# ESP32-S3_4G_LTE_CAT1_V1_2.net
KiCad netlist of a schematic drawn in EAGLE
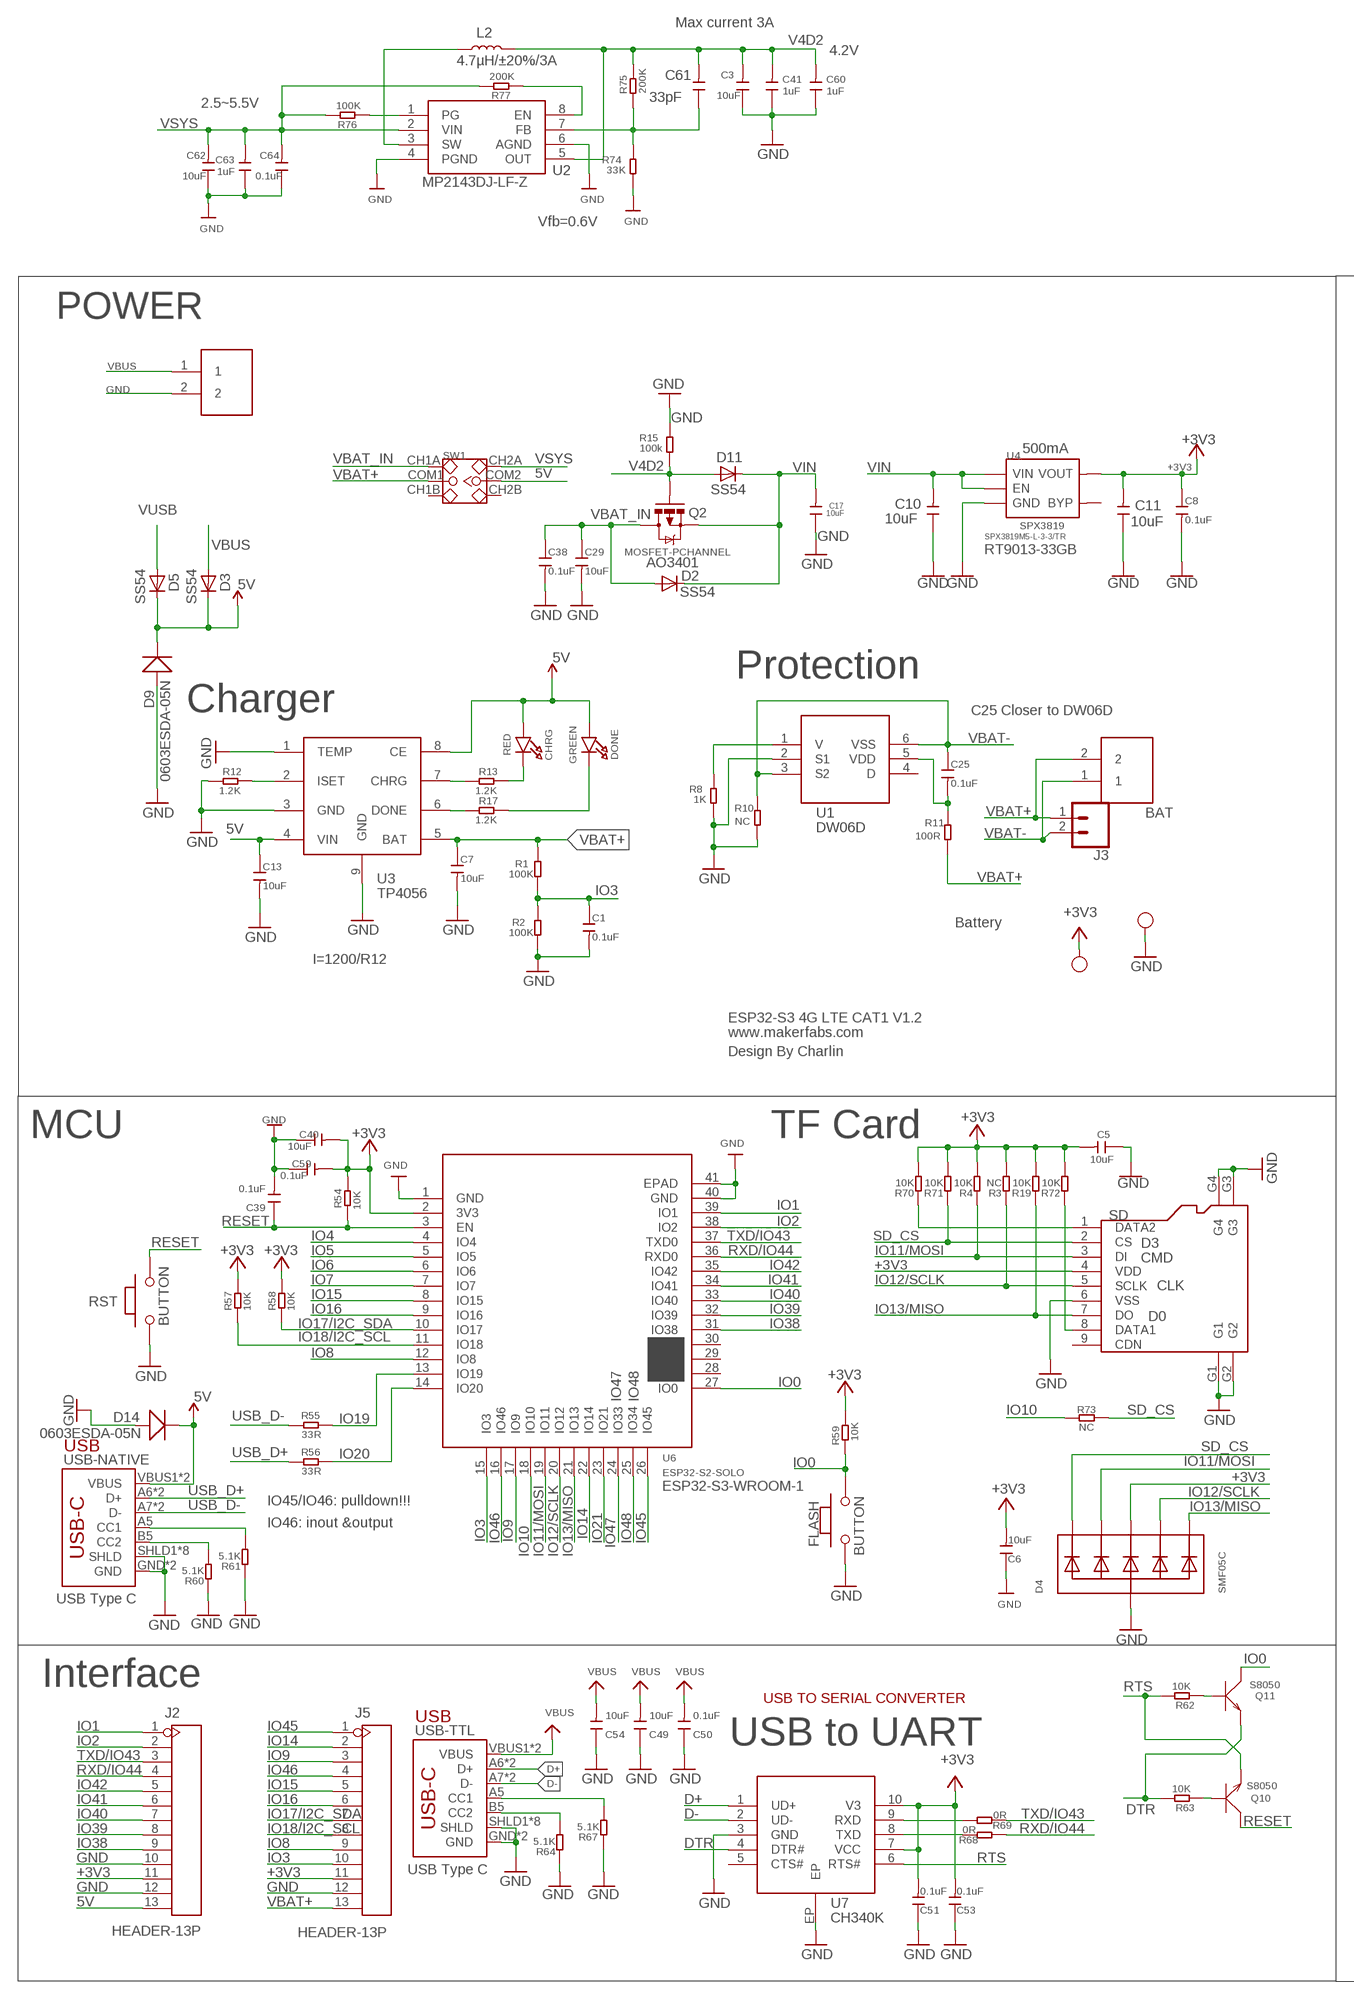
[diagram p0: schematic, sheet 1, part 1 of 2]
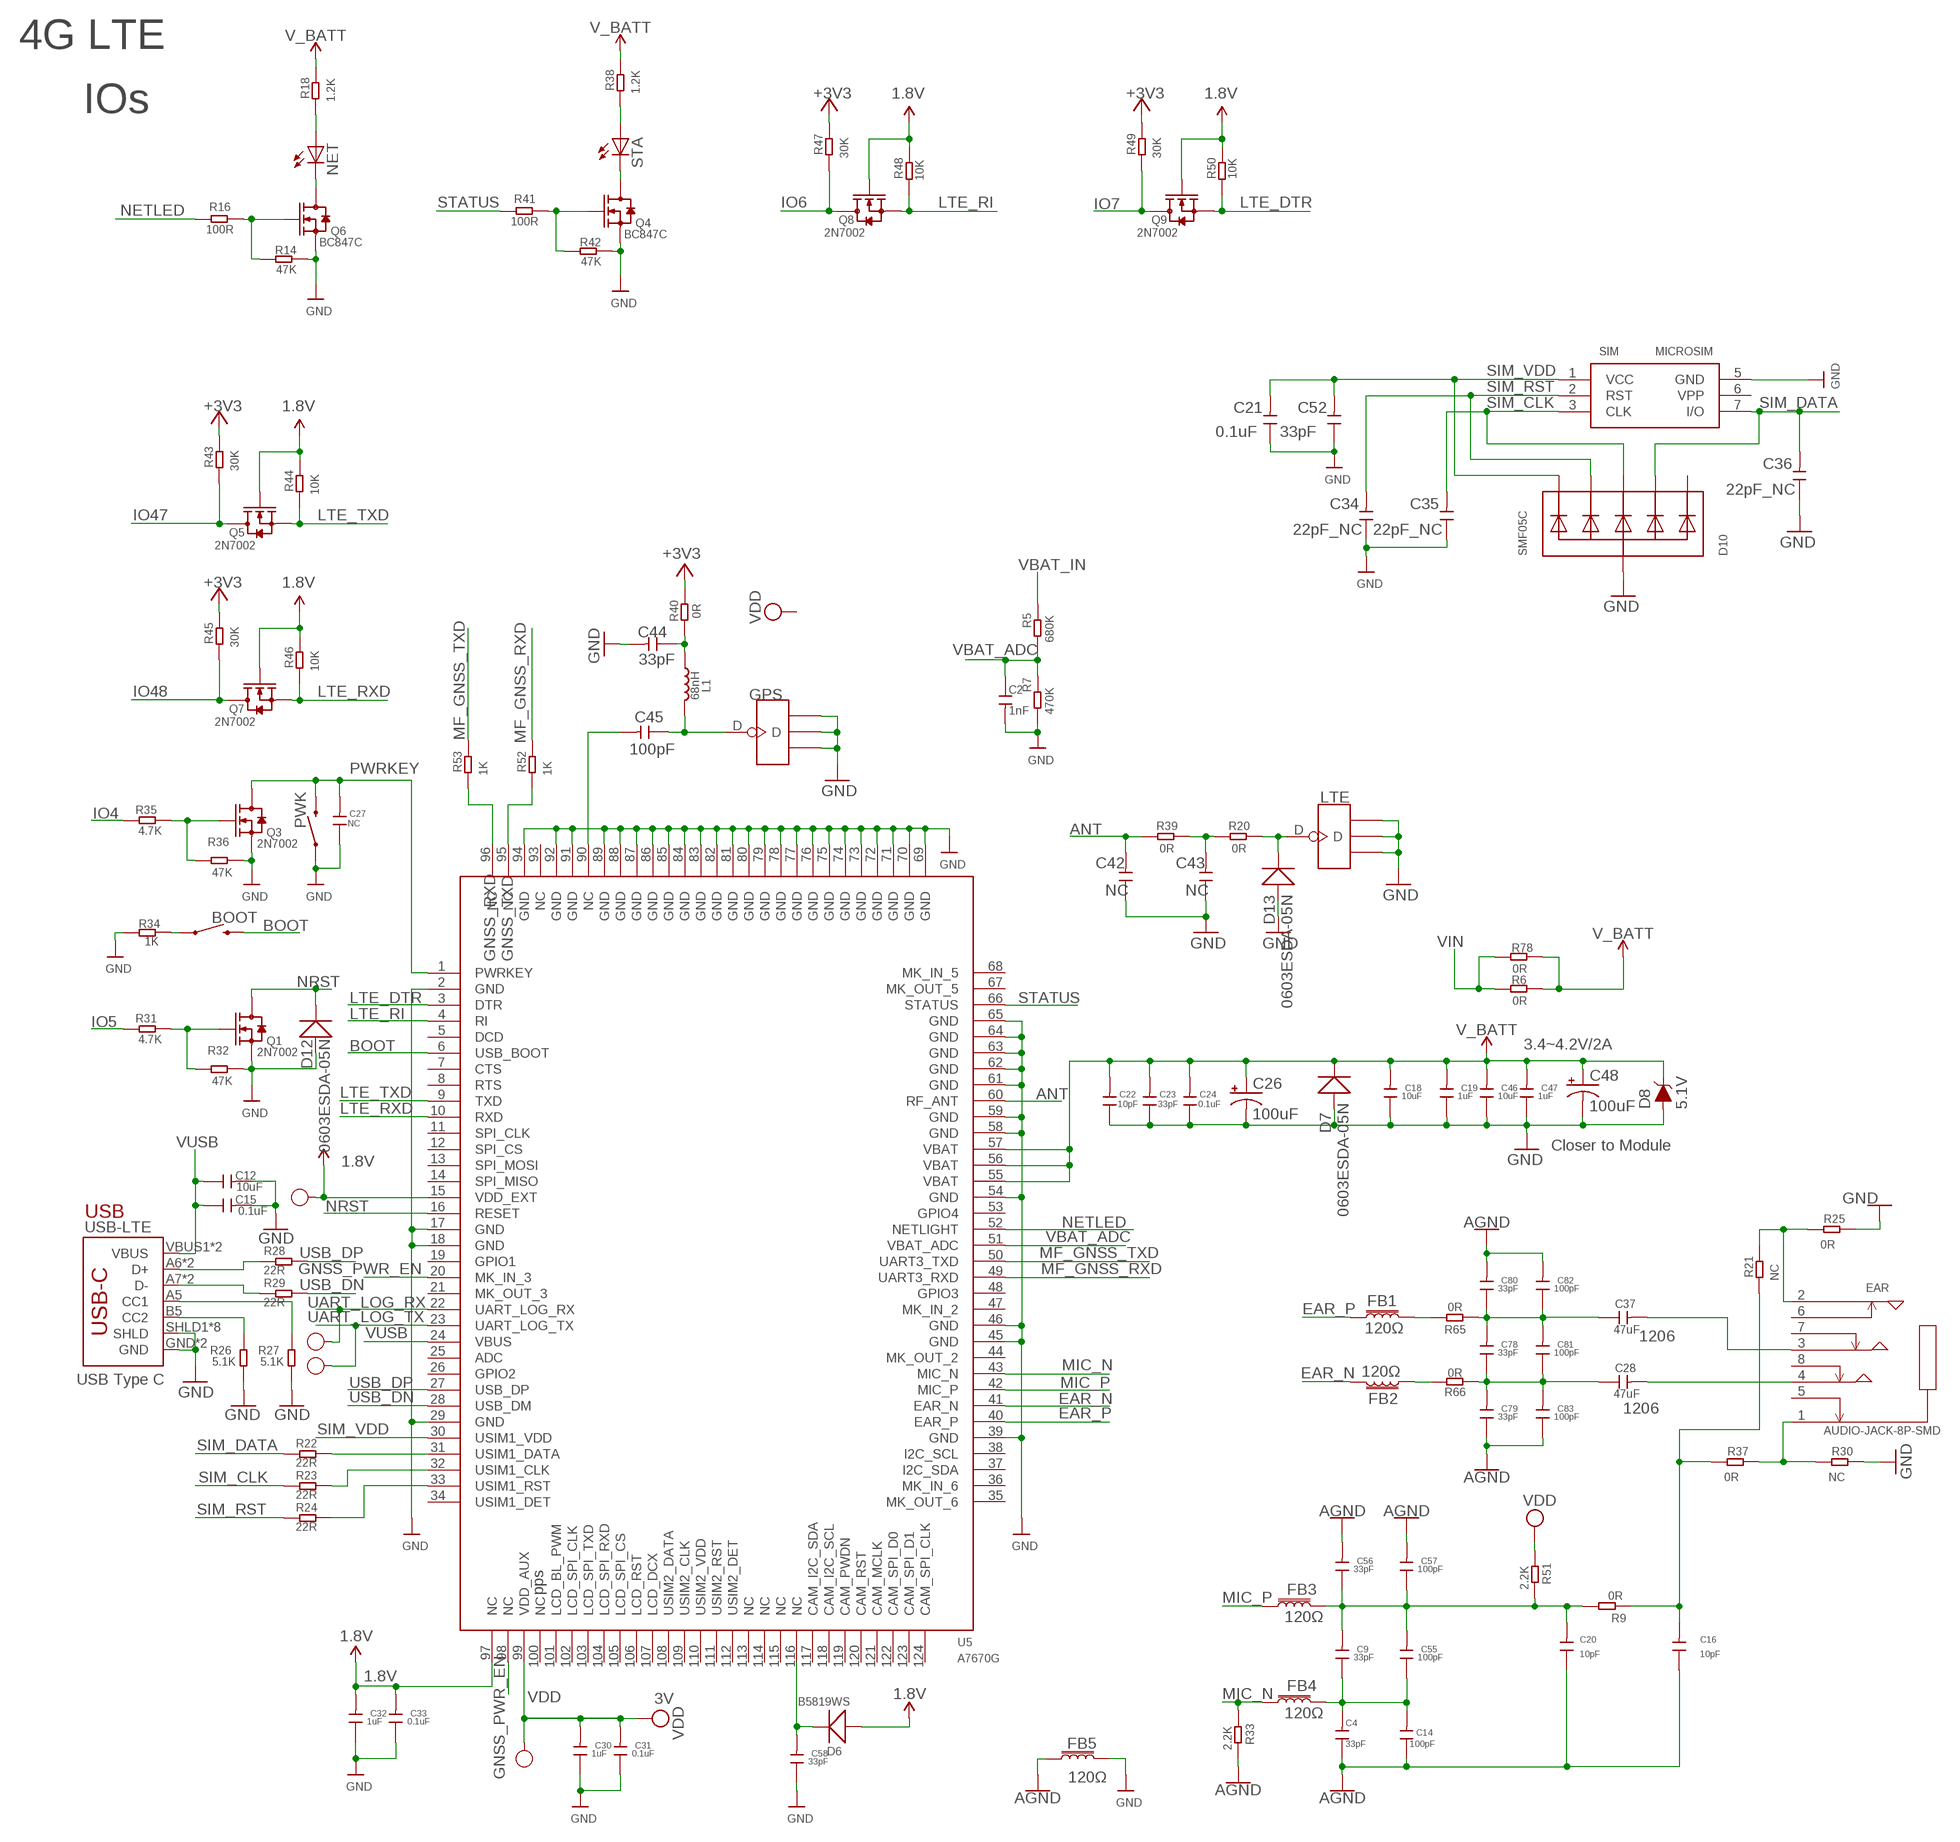
[diagram p1: schematic, sheet 1, part 2 of 2]

(export (version "E")
  (design (tool "Eeschema 10.0.6"))
  (components
    (comp (ref "1V8")
      (value "TEST-POINT'4545'")
      (footprint "eagle-import:TP-D45MIL")
      (fields (field (name "PARTNO") "DNP") (field (name "PARTNO_1") "DNP"))
      (libsource (lib "eagle-import") (part "TEST-POINT'4545'"))
    )
    (comp (ref "3V")
      (value "TEST-POINT'4545'")
      (footprint "eagle-import:TP-D45MIL")
      (fields (field (name "PARTNO") "DNP") (field (name "PARTNO_1") "DNP"))
      (libsource (lib "eagle-import") (part "TEST-POINT'4545'"))
    )
    (comp (ref "3V3")
      (value "TEST-POINT'4545'")
      (footprint "eagle-import:TP-D45MIL")
      (fields (field (name "PARTNO") "DNP") (field (name "PARTNO_1") "DNP"))
      (libsource (lib "eagle-import") (part "TEST-POINT'4545'"))
    )
    (comp (ref "BAT")
      (value "PH2.0-2P-90-DIP")
      (footprint "eagle-import:PH2.0-2P-90-DIP")
      (libsource (lib "eagle-import") (part "PH2.0-2P-90-DIP"))
    )
    (comp (ref "BOOT")
      (value "MOMENTARY-SWITCH-SPST-SMD-6.0X3.5MM")
      (footprint "eagle-import:TACTILE_SWITCH_SMD_6.0X3.5MM")
      (fields (field (name "PROD_ID") "SWCH-00815") (field (name "SF_SKU") "COM-08229"))
      (libsource (lib "eagle-import") (part "MOMENTARY-SWITCH-SPST-SMD-6.0X3.5MM"))
    )
    (comp (ref "C1")
      (value "0.1uF")
      (footprint "eagle-import:0603")
      (libsource (lib "eagle-import") (part "C-0603"))
    )
    (comp (ref "C2")
      (value "1nF")
      (footprint "eagle-import:0603")
      (libsource (lib "eagle-import") (part "C-0603"))
    )
    (comp (ref "C3")
      (value "10uF")
      (footprint "eagle-import:0603")
      (libsource (lib "eagle-import") (part "C-0603"))
    )
    (comp (ref "C4")
      (value "33pF")
      (footprint "eagle-import:0603")
      (libsource (lib "eagle-import") (part "C-0603"))
    )
    (comp (ref "C5")
      (value "10uF")
      (footprint "eagle-import:DISCRETE_C0603")
      (libsource (lib "eagle-import") (part "DISCRETE_C-0603"))
    )
    (comp (ref "C6")
      (value "10uF")
      (footprint "eagle-import:DISCRETE_C0603")
      (libsource (lib "eagle-import") (part "DISCRETE_C-0603"))
    )
    (comp (ref "C7")
      (value "10uF")
      (footprint "eagle-import:0603")
      (libsource (lib "eagle-import") (part "C-0603"))
    )
    (comp (ref "C8")
      (value "0.1uF")
      (footprint "eagle-import:0603")
      (libsource (lib "eagle-import") (part "C-0603"))
    )
    (comp (ref "C9")
      (value "33pF")
      (footprint "eagle-import:0603")
      (libsource (lib "eagle-import") (part "C-0603"))
    )
    (comp (ref "C10")
      (value "10uF")
      (footprint "eagle-import:0603")
      (libsource (lib "eagle-import") (part "C-0603"))
    )
    (comp (ref "C11")
      (value "10uF")
      (footprint "eagle-import:0603")
      (libsource (lib "eagle-import") (part "C-0603"))
    )
    (comp (ref "C12")
      (value "10uF")
      (footprint "eagle-import:0603")
      (libsource (lib "eagle-import") (part "C-0603"))
    )
    (comp (ref "C13")
      (value "10uF")
      (footprint "eagle-import:0603")
      (libsource (lib "eagle-import") (part "C-0603"))
    )
    (comp (ref "C14")
      (value "100pF")
      (footprint "eagle-import:0603")
      (libsource (lib "eagle-import") (part "C-0603"))
    )
    (comp (ref "C15")
      (value "0.1uF")
      (footprint "eagle-import:0603")
      (libsource (lib "eagle-import") (part "C-0603"))
    )
    (comp (ref "C16")
      (value "10pF")
      (footprint "eagle-import:0603")
      (libsource (lib "eagle-import") (part "C-0603"))
    )
    (comp (ref "C17")
      (value "10uF")
      (footprint "eagle-import:0603")
      (libsource (lib "eagle-import") (part "C-0603"))
    )
    (comp (ref "C18")
      (value "10uF")
      (footprint "eagle-import:0603")
      (libsource (lib "eagle-import") (part "C-0603"))
    )
    (comp (ref "C19")
      (value "1uF")
      (footprint "eagle-import:0603")
      (libsource (lib "eagle-import") (part "C-0603"))
    )
    (comp (ref "C20")
      (value "10pF")
      (footprint "eagle-import:0603")
      (libsource (lib "eagle-import") (part "C-0603"))
    )
    (comp (ref "C21")
      (value "0.1uF")
      (footprint "eagle-import:0603")
      (libsource (lib "eagle-import") (part "C-0603"))
    )
    (comp (ref "C22")
      (value "10pF")
      (footprint "eagle-import:0603")
      (libsource (lib "eagle-import") (part "C-0603"))
    )
    (comp (ref "C23")
      (value "33pF")
      (footprint "eagle-import:0603")
      (libsource (lib "eagle-import") (part "C-0603"))
    )
    (comp (ref "C24")
      (value "0.1uF")
      (footprint "eagle-import:0603")
      (libsource (lib "eagle-import") (part "C-0603"))
    )
    (comp (ref "C25")
      (value "0.1uF")
      (footprint "eagle-import:0603")
      (libsource (lib "eagle-import") (part "C-0603"))
    )
    (comp (ref "C26")
      (value "100uF")
      (footprint "eagle-import:EIA3528")
      (fields (field (name "PROD_ID") "CAP-10790"))
      (libsource (lib "eagle-import") (part "68UF-POLAR-EIA3528-10V-10%(TANT)"))
    )
    (comp (ref "C27")
      (value "NC")
      (footprint "eagle-import:0603")
      (libsource (lib "eagle-import") (part "C-0603"))
    )
    (comp (ref "C28")
      (value "47uF")
      (footprint "eagle-import:DISCRETE_C1206")
      (libsource (lib "eagle-import") (part "DISCRETE_C-1206"))
    )
    (comp (ref "C29")
      (value "10uF")
      (footprint "eagle-import:0603")
      (libsource (lib "eagle-import") (part "C-0603"))
    )
    (comp (ref "C30")
      (value "1uF")
      (footprint "eagle-import:0603")
      (libsource (lib "eagle-import") (part "C-0603"))
    )
    (comp (ref "C31")
      (value "0.1uF")
      (footprint "eagle-import:0603")
      (libsource (lib "eagle-import") (part "C-0603"))
    )
    (comp (ref "C32")
      (value "1uF")
      (footprint "eagle-import:0603")
      (libsource (lib "eagle-import") (part "C-0603"))
    )
    (comp (ref "C33")
      (value "0.1uF")
      (footprint "eagle-import:0603")
      (libsource (lib "eagle-import") (part "C-0603"))
    )
    (comp (ref "C34")
      (value "22pF_NC")
      (footprint "eagle-import:0603")
      (libsource (lib "eagle-import") (part "C-0603"))
    )
    (comp (ref "C35")
      (value "22pF_NC")
      (footprint "eagle-import:0603")
      (libsource (lib "eagle-import") (part "C-0603"))
    )
    (comp (ref "C36")
      (value "22pF_NC")
      (footprint "eagle-import:0603")
      (libsource (lib "eagle-import") (part "C-0603"))
    )
    (comp (ref "C37")
      (value "47uF")
      (footprint "eagle-import:DISCRETE_C1206")
      (libsource (lib "eagle-import") (part "DISCRETE_C-1206"))
    )
    (comp (ref "C38")
      (value "0.1uF")
      (footprint "eagle-import:0603")
      (libsource (lib "eagle-import") (part "C-0603"))
    )
    (comp (ref "C39")
      (value "0.1uF")
      (footprint "eagle-import:DISCRETE_C0603")
      (libsource (lib "eagle-import") (part "DISCRETE_C-0603"))
    )
    (comp (ref "C40")
      (value "10uF")
      (footprint "eagle-import:DISCRETE_C0603")
      (libsource (lib "eagle-import") (part "DISCRETE_C-0603"))
    )
    (comp (ref "C41")
      (value "1uF")
      (footprint "eagle-import:0603")
      (libsource (lib "eagle-import") (part "C-0603"))
    )
    (comp (ref "C42")
      (value "NC")
      (footprint "eagle-import:0603")
      (libsource (lib "eagle-import") (part "C-0603"))
    )
    (comp (ref "C43")
      (value "NC")
      (footprint "eagle-import:0603")
      (libsource (lib "eagle-import") (part "C-0603"))
    )
    (comp (ref "C44")
      (value "33pF")
      (footprint "eagle-import:0603")
      (libsource (lib "eagle-import") (part "C-0603"))
    )
    (comp (ref "C45")
      (value "100pF")
      (footprint "eagle-import:0603")
      (libsource (lib "eagle-import") (part "C-0603"))
    )
    (comp (ref "C46")
      (value "10uF")
      (footprint "eagle-import:0603")
      (libsource (lib "eagle-import") (part "C-0603"))
    )
    (comp (ref "C47")
      (value "1uF")
      (footprint "eagle-import:0603")
      (libsource (lib "eagle-import") (part "C-0603"))
    )
    (comp (ref "C48")
      (value "100uF")
      (footprint "eagle-import:EIA3528")
      (libsource (lib "eagle-import") (part "68UF-POLAR-EIA3528-10V-10%(TANT)"))
    )
    (comp (ref "C49")
      (value "10uF")
      (footprint "eagle-import:DISCRETE_C0603")
      (libsource (lib "eagle-import") (part "DISCRETE_C-0603"))
    )
    (comp (ref "C50")
      (value "0.1uF")
      (footprint "eagle-import:DISCRETE_C0603")
      (libsource (lib "eagle-import") (part "DISCRETE_C-0603"))
    )
    (comp (ref "C51")
      (value "0.1uF")
      (footprint "eagle-import:DISCRETE_C0603")
      (libsource (lib "eagle-import") (part "DISCRETE_C-0603"))
    )
    (comp (ref "C52")
      (value "33pF")
      (footprint "eagle-import:0603")
      (libsource (lib "eagle-import") (part "C-0603"))
    )
    (comp (ref "C53")
      (value "0.1uF")
      (footprint "eagle-import:DISCRETE_C0603")
      (libsource (lib "eagle-import") (part "DISCRETE_C-0603"))
    )
    (comp (ref "C54")
      (value "10uF")
      (footprint "eagle-import:DISCRETE_C0603")
      (libsource (lib "eagle-import") (part "DISCRETE_C-0603"))
    )
    (comp (ref "C55")
      (value "100pF")
      (footprint "eagle-import:0603")
      (libsource (lib "eagle-import") (part "C-0603"))
    )
    (comp (ref "C56")
      (value "33pF")
      (footprint "eagle-import:0603")
      (libsource (lib "eagle-import") (part "C-0603"))
    )
    (comp (ref "C57")
      (value "100pF")
      (footprint "eagle-import:0603")
      (libsource (lib "eagle-import") (part "C-0603"))
    )
    (comp (ref "C58")
      (value "33pF")
      (footprint "eagle-import:0603")
      (libsource (lib "eagle-import") (part "C-0603"))
    )
    (comp (ref "C59")
      (value "0.1uF")
      (footprint "eagle-import:DISCRETE_C0603")
      (libsource (lib "eagle-import") (part "DISCRETE_C-0603"))
    )
    (comp (ref "C60")
      (value "1uF")
      (footprint "eagle-import:0603")
      (libsource (lib "eagle-import") (part "C-0603"))
    )
    (comp (ref "C61")
      (value "33pF")
      (footprint "eagle-import:0603")
      (libsource (lib "eagle-import") (part "C-0603"))
    )
    (comp (ref "C62")
      (value "10uF")
      (footprint "eagle-import:0603")
      (libsource (lib "eagle-import") (part "C-0603"))
    )
    (comp (ref "C63")
      (value "1uF")
      (footprint "eagle-import:0603")
      (libsource (lib "eagle-import") (part "C-0603"))
    )
    (comp (ref "C64")
      (value "0.1uF")
      (footprint "eagle-import:0603")
      (libsource (lib "eagle-import") (part "C-0603"))
    )
    (comp (ref "C78")
      (value "33pF")
      (footprint "eagle-import:0603")
      (libsource (lib "eagle-import") (part "C-0603"))
    )
    (comp (ref "C79")
      (value "33pF")
      (footprint "eagle-import:0603")
      (libsource (lib "eagle-import") (part "C-0603"))
    )
    (comp (ref "C80")
      (value "33pF")
      (footprint "eagle-import:0603")
      (libsource (lib "eagle-import") (part "C-0603"))
    )
    (comp (ref "C81")
      (value "100pF")
      (footprint "eagle-import:0603")
      (libsource (lib "eagle-import") (part "C-0603"))
    )
    (comp (ref "C82")
      (value "100pF")
      (footprint "eagle-import:0603")
      (libsource (lib "eagle-import") (part "C-0603"))
    )
    (comp (ref "C83")
      (value "100pF")
      (footprint "eagle-import:0603")
      (libsource (lib "eagle-import") (part "C-0603"))
    )
    (comp (ref "CHRG")
      (value "RED")
      (footprint "eagle-import:CHIPLED_0805_NOOUTLINE")
      (libsource (lib "eagle-import") (part "LED0805_NOOUTLINE"))
    )
    (comp (ref "D2")
      (value "SS54")
      (footprint "eagle-import:DO-214AC")
      (libsource (lib "eagle-import") (part "DIODE-DO-214AC"))
    )
    (comp (ref "D3")
      (value "SS54")
      (footprint "eagle-import:DO-214AC")
      (libsource (lib "eagle-import") (part "DIODE-DO-214AC"))
    )
    (comp (ref "D4")
      (value "SMF05C")
      (footprint "eagle-import:SOT363")
      (libsource (lib "eagle-import") (part "TVSARRAY_5LANE"))
    )
    (comp (ref "D5")
      (value "SS54")
      (footprint "eagle-import:DO-214AC")
      (libsource (lib "eagle-import") (part "DIODE-DO-214AC"))
    )
    (comp (ref "D6")
      (value "B5819WS")
      (footprint "eagle-import:SOD323")
      (libsource (lib "eagle-import") (part "D'0805'"))
    )
    (comp (ref "D7")
      (value "0603ESDA-05N")
      (footprint "eagle-import:DISCRETE_SOD523")
      (libsource (lib "eagle-import") (part "DISCRETE_D0603"))
    )
    (comp (ref "D8")
      (value "5.1V")
      (footprint "eagle-import:SOD-323")
      (libsource (lib "eagle-import") (part "DIODE-ZENER-MMSZ5232BS"))
    )
    (comp (ref "D9")
      (value "0603ESDA-05N")
      (footprint "eagle-import:DISCRETE_SOD523")
      (libsource (lib "eagle-import") (part "DISCRETE_D0603"))
    )
    (comp (ref "D10")
      (value "SMF05C")
      (footprint "eagle-import:SOT363")
      (libsource (lib "eagle-import") (part "TVSARRAY_5LANE"))
    )
    (comp (ref "D11")
      (value "SS54")
      (footprint "eagle-import:DO-214AC")
      (libsource (lib "eagle-import") (part "DIODE-DO-214AC"))
    )
    (comp (ref "D12")
      (value "0603ESDA-05N")
      (footprint "eagle-import:DISCRETE_SOD523")
      (libsource (lib "eagle-import") (part "DISCRETE_D0603"))
    )
    (comp (ref "D13")
      (value "0603ESDA-05N")
      (footprint "eagle-import:DISCRETE_SOD523")
      (libsource (lib "eagle-import") (part "DISCRETE_D0603"))
    )
    (comp (ref "D14")
      (value "0603ESDA-05N")
      (footprint "eagle-import:DISCRETE_SOD523")
      (libsource (lib "eagle-import") (part "DISCRETE_D0603"))
    )
    (comp (ref "DONE")
      (value "GREEN")
      (footprint "eagle-import:CHIPLED_0805_NOOUTLINE")
      (libsource (lib "eagle-import") (part "LED0805_NOOUTLINE"))
    )
    (comp (ref "EAR")
      (value "AUDIO-JACK-8P-SMD")
      (footprint "eagle-import:AUDIO8P-SMD-3.5-14.5X6.1X4.0MM")
      (libsource (lib "eagle-import") (part "AUDIO-JACK-8P-SMD'PJ-393'"))
    )
    (comp (ref "FB1")
      (value "120Ω")
      (footprint "eagle-import:0603")
      (libsource (lib "eagle-import") (part "FERRITE_BEAD-0603"))
    )
    (comp (ref "FB2")
      (value "120Ω")
      (footprint "eagle-import:0603")
      (fields (field (name "PROD_ID") "NDUC-13805"))
      (libsource (lib "eagle-import") (part "FERRITE_BEAD-0603"))
    )
    (comp (ref "FB3")
      (value "120Ω")
      (footprint "eagle-import:0603")
      (fields (field (name "PROD_ID") "NDUC-13805"))
      (libsource (lib "eagle-import") (part "FERRITE_BEAD-0603"))
    )
    (comp (ref "FB4")
      (value "120Ω")
      (footprint "eagle-import:0603")
      (fields (field (name "PROD_ID") "NDUC-13805"))
      (libsource (lib "eagle-import") (part "FERRITE_BEAD-0603"))
    )
    (comp (ref "FB5")
      (value "120Ω")
      (footprint "eagle-import:0603")
      (fields (field (name "PROD_ID") "NDUC-13805"))
      (libsource (lib "eagle-import") (part "FERRITE_BEAD-0603"))
    )
    (comp (ref "FLASH")
      (value "BUTTON")
      (footprint "eagle-import:157SW")
      (libsource (lib "eagle-import") (part "PB157"))
    )
    (comp (ref "GND")
      (value "TEST-POINT'4545'")
      (footprint "eagle-import:TP-D45MIL")
      (fields (field (name "PARTNO") "DNP") (field (name "PARTNO_1") "DNP"))
      (libsource (lib "eagle-import") (part "TEST-POINT'4545'"))
    )
    (comp (ref "GPS")
      (value "ANTENNA-U-FL")
      (footprint "eagle-import:4P-U-FL")
      (libsource (lib "eagle-import") (part "ANTENNA-U-FL"))
    )
    (comp (ref "J1")
      (value "PH2.0-2P-90-DIP")
      (footprint "eagle-import:PH2.0-2P-90-DIP")
      (libsource (lib "eagle-import") (part "PH2.0-2P-90-DIP"))
    )
    (comp (ref "J2")
      (value "HEADER-13P")
      (footprint "eagle-import:13P-2.54")
      (libsource (lib "eagle-import") (part "HEADER-13P"))
    )
    (comp (ref "J3")
      (value "CONN_02LOCK")
      (footprint "eagle-import:1X02_LOCK")
      (libsource (lib "eagle-import") (part "CONN_02LOCK"))
    )
    (comp (ref "J5")
      (value "HEADER-13P")
      (footprint "eagle-import:13P-2.54")
      (libsource (lib "eagle-import") (part "HEADER-13P"))
    )
    (comp (ref "L1")
      (value "68nH")
      (footprint "eagle-import:L0603")
      (libsource (lib "eagle-import") (part "L'0603'"))
    )
    (comp (ref "L2")
      (value "4.7µH/±20%/3A")
      (footprint "eagle-import:SRN6045")
      (libsource (lib "eagle-import") (part "INDUCTOR-SRN6045-33UH"))
    )
    (comp (ref "LTE")
      (value "ANTENNA-U-FL")
      (footprint "eagle-import:4P-U-FL")
      (libsource (lib "eagle-import") (part "ANTENNA-U-FL"))
    )
    (comp (ref "NET")
      (value "NET")
      (footprint "eagle-import:CHIP-LED0805")
      (libsource (lib "eagle-import") (part "LEDCHIP-LED0805"))
    )
    (comp (ref "PWK")
      (value "MOMENTARY-SWITCH-SPST-SMD-6.0X3.5MM")
      (footprint "eagle-import:TACTILE_SWITCH_SMD_6.0X3.5MM")
      (libsource (lib "eagle-import") (part "MOMENTARY-SWITCH-SPST-SMD-6.0X3.5MM"))
    )
    (comp (ref "Q1")
      (value "2N7002")
      (footprint "eagle-import:SOT23")
      (libsource (lib "eagle-import") (part "MOSFET-N'SOT23'"))
    )
    (comp (ref "Q2")
      (value "MOSFET-PCHANNEL")
      (footprint "eagle-import:SOT23-3")
      (libsource (lib "eagle-import") (part "MOSFET-PCHANNEL"))
    )
    (comp (ref "Q3")
      (value "2N7002")
      (footprint "eagle-import:SOT23")
      (libsource (lib "eagle-import") (part "MOSFET-N'SOT23'"))
    )
    (comp (ref "Q4")
      (value "BC847C")
      (footprint "eagle-import:SOT23")
      (libsource (lib "eagle-import") (part "MOSFET-N'SOT23'"))
    )
    (comp (ref "Q5")
      (value "2N7002")
      (footprint "eagle-import:SOT23")
      (libsource (lib "eagle-import") (part "MOSFET-N'SOT23'"))
    )
    (comp (ref "Q6")
      (value "BC847C")
      (footprint "eagle-import:SOT23")
      (libsource (lib "eagle-import") (part "MOSFET-N'SOT23'"))
    )
    (comp (ref "Q7")
      (value "2N7002")
      (footprint "eagle-import:SOT23")
      (libsource (lib "eagle-import") (part "MOSFET-N'SOT23'"))
    )
    (comp (ref "Q8")
      (value "2N7002")
      (footprint "eagle-import:SOT23")
      (libsource (lib "eagle-import") (part "MOSFET-N'SOT23'"))
    )
    (comp (ref "Q9")
      (value "2N7002")
      (footprint "eagle-import:SOT23")
      (libsource (lib "eagle-import") (part "MOSFET-N'SOT23'"))
    )
    (comp (ref "Q10")
      (value "S8050")
      (footprint "eagle-import:SOT23")
      (libsource (lib "eagle-import") (part "TRANSISTOR-NPN-SOT23"))
    )
    (comp (ref "Q11")
      (value "S8050")
      (footprint "eagle-import:SOT23")
      (libsource (lib "eagle-import") (part "TRANSISTOR-NPN-SOT23"))
    )
    (comp (ref "R1")
      (value "100K")
      (footprint "eagle-import:R0603")
      (libsource (lib "eagle-import") (part "R-0603"))
    )
    (comp (ref "R2")
      (value "100K")
      (footprint "eagle-import:R0603")
      (libsource (lib "eagle-import") (part "R-0603"))
    )
    (comp (ref "R3")
      (value "NC")
      (footprint "eagle-import:DISCRETE_R0603")
      (libsource (lib "eagle-import") (part "DISCRETE_R-0603"))
    )
    (comp (ref "R4")
      (value "10K")
      (footprint "eagle-import:DISCRETE_R0603")
      (libsource (lib "eagle-import") (part "DISCRETE_R-0603"))
    )
    (comp (ref "R5")
      (value "680K")
      (footprint "eagle-import:R0603")
      (libsource (lib "eagle-import") (part "R-0603"))
    )
    (comp (ref "R6")
      (value "0R")
      (footprint "eagle-import:R0603")
      (libsource (lib "eagle-import") (part "R-0603"))
    )
    (comp (ref "R7")
      (value "470K")
      (footprint "eagle-import:R0603")
      (libsource (lib "eagle-import") (part "R-0603"))
    )
    (comp (ref "R8")
      (value "1K")
      (footprint "eagle-import:R0603")
      (libsource (lib "eagle-import") (part "R-0603"))
    )
    (comp (ref "R9")
      (value "0R")
      (footprint "eagle-import:R0603")
      (libsource (lib "eagle-import") (part "R-0603"))
    )
    (comp (ref "R10")
      (value "NC")
      (footprint "eagle-import:R0603")
      (libsource (lib "eagle-import") (part "R-0603"))
    )
    (comp (ref "R11")
      (value "100R")
      (footprint "eagle-import:R0603")
      (libsource (lib "eagle-import") (part "R-0603"))
    )
    (comp (ref "R12")
      (value "1.2K")
      (footprint "eagle-import:R0603")
      (libsource (lib "eagle-import") (part "R-0603"))
    )
    (comp (ref "R13")
      (value "1.2K")
      (footprint "eagle-import:R0603")
      (libsource (lib "eagle-import") (part "R-0603"))
    )
    (comp (ref "R14")
      (value "47K")
      (footprint "eagle-import:R0603")
      (libsource (lib "eagle-import") (part "R-0603"))
    )
    (comp (ref "R15")
      (value "100k")
      (footprint "eagle-import:R0603")
      (libsource (lib "eagle-import") (part "R-0603"))
    )
    (comp (ref "R16")
      (value "100R")
      (footprint "eagle-import:R0603")
      (libsource (lib "eagle-import") (part "R-0603"))
    )
    (comp (ref "R17")
      (value "1.2K")
      (footprint "eagle-import:R0603")
      (libsource (lib "eagle-import") (part "R-0603"))
    )
    (comp (ref "R18")
      (value "1.2K")
      (footprint "eagle-import:R0603")
      (libsource (lib "eagle-import") (part "R-0603"))
    )
    (comp (ref "R19")
      (value "10K")
      (footprint "eagle-import:DISCRETE_R0603")
      (libsource (lib "eagle-import") (part "DISCRETE_R-0603"))
    )
    (comp (ref "R20")
      (value "0R")
      (footprint "eagle-import:R0603")
      (libsource (lib "eagle-import") (part "R-0603"))
    )
    (comp (ref "R21")
      (value "NC")
      (footprint "eagle-import:R0603")
      (libsource (lib "eagle-import") (part "R-0603"))
    )
    (comp (ref "R22")
      (value "22R")
      (footprint "eagle-import:R0603")
      (libsource (lib "eagle-import") (part "R-0603"))
    )
    (comp (ref "R23")
      (value "22R")
      (footprint "eagle-import:R0603")
      (libsource (lib "eagle-import") (part "R-0603"))
    )
    (comp (ref "R24")
      (value "22R")
      (footprint "eagle-import:R0603")
      (libsource (lib "eagle-import") (part "R-0603"))
    )
    (comp (ref "R25")
      (value "0R")
      (footprint "eagle-import:R0603")
      (libsource (lib "eagle-import") (part "R-0603"))
    )
    (comp (ref "R26")
      (value "5.1K")
      (footprint "eagle-import:R0603")
      (libsource (lib "eagle-import") (part "R-0603"))
    )
    (comp (ref "R27")
      (value "5.1K")
      (footprint "eagle-import:R0603")
      (libsource (lib "eagle-import") (part "R-0603"))
    )
    (comp (ref "R28")
      (value "22R")
      (footprint "eagle-import:R0603")
      (libsource (lib "eagle-import") (part "R-0603"))
    )
    (comp (ref "R29")
      (value "22R")
      (footprint "eagle-import:R0603")
      (libsource (lib "eagle-import") (part "R-0603"))
    )
    (comp (ref "R30")
      (value "NC")
      (footprint "eagle-import:R0603")
      (libsource (lib "eagle-import") (part "R-0603"))
    )
    (comp (ref "R31")
      (value "4.7K")
      (footprint "eagle-import:R0603")
      (libsource (lib "eagle-import") (part "R-0603"))
    )
    (comp (ref "R32")
      (value "47K")
      (footprint "eagle-import:R0603")
      (libsource (lib "eagle-import") (part "R-0603"))
    )
    (comp (ref "R33")
      (value "2.2K")
      (footprint "eagle-import:R0603")
      (libsource (lib "eagle-import") (part "R-0603"))
    )
    (comp (ref "R34")
      (value "1K")
      (footprint "eagle-import:R0603")
      (libsource (lib "eagle-import") (part "R-0603"))
    )
    (comp (ref "R35")
      (value "4.7K")
      (footprint "eagle-import:R0603")
      (libsource (lib "eagle-import") (part "R-0603"))
    )
    (comp (ref "R36")
      (value "47K")
      (footprint "eagle-import:R0603")
      (libsource (lib "eagle-import") (part "R-0603"))
    )
    (comp (ref "R37")
      (value "0R")
      (footprint "eagle-import:R0603")
      (libsource (lib "eagle-import") (part "R-0603"))
    )
    (comp (ref "R38")
      (value "1.2K")
      (footprint "eagle-import:R0603")
      (libsource (lib "eagle-import") (part "R-0603"))
    )
    (comp (ref "R39")
      (value "0R")
      (footprint "eagle-import:R0603")
      (libsource (lib "eagle-import") (part "R-0603"))
    )
    (comp (ref "R40")
      (value "0R")
      (footprint "eagle-import:R0603")
      (libsource (lib "eagle-import") (part "R-0603"))
    )
    (comp (ref "R41")
      (value "100R")
      (footprint "eagle-import:R0603")
      (libsource (lib "eagle-import") (part "R-0603"))
    )
    (comp (ref "R42")
      (value "47K")
      (footprint "eagle-import:R0603")
      (libsource (lib "eagle-import") (part "R-0603"))
    )
    (comp (ref "R43")
      (value "30K")
      (footprint "eagle-import:R0603")
      (libsource (lib "eagle-import") (part "R-0603"))
    )
    (comp (ref "R44")
      (value "10K")
      (footprint "eagle-import:R0603")
      (libsource (lib "eagle-import") (part "R-0603"))
    )
    (comp (ref "R45")
      (value "30K")
      (footprint "eagle-import:R0603")
      (libsource (lib "eagle-import") (part "R-0603"))
    )
    (comp (ref "R46")
      (value "10K")
      (footprint "eagle-import:R0603")
      (libsource (lib "eagle-import") (part "R-0603"))
    )
    (comp (ref "R47")
      (value "30K")
      (footprint "eagle-import:R0603")
      (libsource (lib "eagle-import") (part "R-0603"))
    )
    (comp (ref "R48")
      (value "10K")
      (footprint "eagle-import:R0603")
      (libsource (lib "eagle-import") (part "R-0603"))
    )
    (comp (ref "R49")
      (value "30K")
      (footprint "eagle-import:R0603")
      (libsource (lib "eagle-import") (part "R-0603"))
    )
    (comp (ref "R50")
      (value "10K")
      (footprint "eagle-import:R0603")
      (libsource (lib "eagle-import") (part "R-0603"))
    )
    (comp (ref "R51")
      (value "2.2K")
      (footprint "eagle-import:R0603")
      (libsource (lib "eagle-import") (part "R-0603"))
    )
    (comp (ref "R52")
      (value "1K")
      (footprint "eagle-import:R0603")
      (libsource (lib "eagle-import") (part "R-0603"))
    )
    (comp (ref "R53")
      (value "1K")
      (footprint "eagle-import:R0603")
      (libsource (lib "eagle-import") (part "R-0603"))
    )
    (comp (ref "R54")
      (value "10K")
      (footprint "eagle-import:R0603")
      (libsource (lib "eagle-import") (part "R-0603"))
    )
    (comp (ref "R55")
      (value "33R")
      (footprint "eagle-import:R0603")
      (libsource (lib "eagle-import") (part "R-0603"))
    )
    (comp (ref "R56")
      (value "33R")
      (footprint "eagle-import:R0603")
      (libsource (lib "eagle-import") (part "R-0603"))
    )
    (comp (ref "R57")
      (value "10K")
      (footprint "eagle-import:R0603")
      (libsource (lib "eagle-import") (part "R-0603"))
    )
    (comp (ref "R58")
      (value "10K")
      (footprint "eagle-import:R0603")
      (libsource (lib "eagle-import") (part "R-0603"))
    )
    (comp (ref "R59")
      (value "10K")
      (footprint "eagle-import:R0603")
      (libsource (lib "eagle-import") (part "R-0603"))
    )
    (comp (ref "R60")
      (value "5.1K")
      (footprint "eagle-import:DISCRETE_R0603")
      (libsource (lib "eagle-import") (part "DISCRETE_R-0603"))
    )
    (comp (ref "R61")
      (value "5.1K")
      (footprint "eagle-import:DISCRETE_R0603")
      (libsource (lib "eagle-import") (part "DISCRETE_R-0603"))
    )
    (comp (ref "R62")
      (value "10K")
      (footprint "eagle-import:R0603")
      (libsource (lib "eagle-import") (part "R-0603"))
    )
    (comp (ref "R63")
      (value "10K")
      (footprint "eagle-import:R0603")
      (libsource (lib "eagle-import") (part "R-0603"))
    )
    (comp (ref "R64")
      (value "5.1K")
      (footprint "eagle-import:DISCRETE_R0603")
      (libsource (lib "eagle-import") (part "DISCRETE_R-0603"))
    )
    (comp (ref "R65")
      (value "0R")
      (footprint "eagle-import:R0603")
      (libsource (lib "eagle-import") (part "R-0603"))
    )
    (comp (ref "R66")
      (value "0R")
      (footprint "eagle-import:R0603")
      (libsource (lib "eagle-import") (part "R-0603"))
    )
    (comp (ref "R67")
      (value "5.1K")
      (footprint "eagle-import:DISCRETE_R0603")
      (libsource (lib "eagle-import") (part "DISCRETE_R-0603"))
    )
    (comp (ref "R68")
      (value "0R")
      (footprint "eagle-import:R0603")
      (libsource (lib "eagle-import") (part "R-0603"))
    )
    (comp (ref "R69")
      (value "0R")
      (footprint "eagle-import:R0603")
      (libsource (lib "eagle-import") (part "R-0603"))
    )
    (comp (ref "R70")
      (value "10K")
      (footprint "eagle-import:DISCRETE_R0603")
      (libsource (lib "eagle-import") (part "DISCRETE_R-0603"))
    )
    (comp (ref "R71")
      (value "10K")
      (footprint "eagle-import:DISCRETE_R0603")
      (libsource (lib "eagle-import") (part "DISCRETE_R-0603"))
    )
    (comp (ref "R72")
      (value "10K")
      (footprint "eagle-import:DISCRETE_R0603")
      (libsource (lib "eagle-import") (part "DISCRETE_R-0603"))
    )
    (comp (ref "R73")
      (value "NC")
      (footprint "eagle-import:R0603")
      (libsource (lib "eagle-import") (part "R-0603"))
    )
    (comp (ref "R74")
      (value "33K")
      (footprint "eagle-import:R0603")
      (libsource (lib "eagle-import") (part "R-0603"))
    )
    (comp (ref "R75")
      (value "200K")
      (footprint "eagle-import:R0603")
      (libsource (lib "eagle-import") (part "R-0603"))
    )
    (comp (ref "R76")
      (value "100K")
      (footprint "eagle-import:R0603")
      (libsource (lib "eagle-import") (part "R-0603"))
    )
    (comp (ref "R77")
      (value "200K")
      (footprint "eagle-import:R0603")
      (libsource (lib "eagle-import") (part "R-0603"))
    )
    (comp (ref "R78")
      (value "0R")
      (footprint "eagle-import:R0603")
      (libsource (lib "eagle-import") (part "R-0603"))
    )
    (comp (ref "RST")
      (value "BUTTON")
      (footprint "eagle-import:157SW")
      (libsource (lib "eagle-import") (part "PB157"))
    )
    (comp (ref "RX")
      (value "TEST-POINT'4545'")
      (footprint "eagle-import:TP-D45MIL")
      (fields (field (name "PARTNO") "DNP") (field (name "PARTNO_1") "DNP"))
      (libsource (lib "eagle-import") (part "TEST-POINT'4545'"))
    )
    (comp (ref "SD")
      (value "HOLDER-MICROSD-9P")
      (footprint "eagle-import:9P-SMD-W_-RING")
      (libsource (lib "eagle-import") (part "HOLDER-MICROSD-9P"))
    )
    (comp (ref "SIM")
      (value "MICROSIM")
      (footprint "eagle-import:MICROSIM")
      (libsource (lib "eagle-import") (part "MICROSIM"))
    )
    (comp (ref "STA")
      (value "NET")
      (footprint "eagle-import:CHIP-LED0805")
      (libsource (lib "eagle-import") (part "LEDCHIP-LED0805"))
    )
    (comp (ref "SW1")
      (value "SWITCH-2CH-6P")
      (footprint "eagle-import:6P-2CH-2.54-7.6X3.0")
      (libsource (lib "eagle-import") (part "SWITCH-2CH-6P"))
    )
    (comp (ref "TX")
      (value "TEST-POINT'4545'")
      (footprint "eagle-import:TP-D45MIL")
      (fields (field (name "PARTNO") "DNP") (field (name "PARTNO_1") "DNP"))
      (libsource (lib "eagle-import") (part "TEST-POINT'4545'"))
    )
    (comp (ref "U1")
      (value "DW06D")
      (footprint "eagle-import:SOT-23-6")
      (libsource (lib "eagle-import") (part "DW06D"))
    )
    (comp (ref "U2")
      (value "MP2143DJ-LF-Z")
      (footprint "eagle-import:TSOT23-8")
      (libsource (lib "eagle-import") (part "MP2143DJ-LF-Z"))
    )
    (comp (ref "U3")
      (value "TP4056")
      (footprint "eagle-import:SOP8-1.27P")
      (libsource (lib "eagle-import") (part "TP4056"))
    )
    (comp (ref "U4")
      (value "SPX3819")
      (footprint "eagle-import:SOT23-5")
      (libsource (lib "eagle-import") (part "SPX3819"))
    )
    (comp (ref "U5")
      (value "A7670G")
      (footprint "eagle-import:A7670G")
      (libsource (lib "eagle-import") (part "A7670G"))
    )
    (comp (ref "U6")
      (value "ESP32­S2­SOLO")
      (footprint "eagle-import:ESP32-­S2-­SOLO")
      (libsource (lib "eagle-import") (part "ESP32­S2­SOLO"))
    )
    (comp (ref "U7")
      (value "CH340K")
      (footprint "eagle-import:ESOP-10-EP-150MIL")
      (libsource (lib "eagle-import") (part "CH340K"))
    )
    (comp (ref "USB-LTE")
      (value "USB_C5")
      (footprint "eagle-import:USB-C-16P-5")
      (libsource (lib "eagle-import") (part "USB_C5"))
    )
    (comp (ref "USB-NATIVE")
      (value "USB_C5")
      (footprint "eagle-import:USB-C-16P-5")
      (libsource (lib "eagle-import") (part "USB_C5"))
    )
    (comp (ref "USB-TTL")
      (value "USB_C5")
      (footprint "eagle-import:USB-C-16P-5")
      (libsource (lib "eagle-import") (part "USB_C5"))
    )
  )
  (nets
    (net (code "1") (name "+3V3") (class "Default")
      (node (ref "3V3") (pin "T") (pinfunction "T_T") (pintype "bidirectional"))
      (node (ref "C11") (pin "2") (pinfunction "2_2") (pintype "passive"))
      (node (ref "C40") (pin "2") (pinfunction "2_2") (pintype "passive"))
      (node (ref "C5") (pin "2") (pinfunction "2_2") (pintype "passive"))
      (node (ref "C51") (pin "2") (pinfunction "2_2") (pintype "passive"))
      (node (ref "C53") (pin "2") (pinfunction "2_2") (pintype "passive"))
      (node (ref "C59") (pin "2") (pinfunction "2_2") (pintype "passive"))
      (node (ref "C6") (pin "2") (pinfunction "2_2") (pintype "passive"))
      (node (ref "C8") (pin "1") (pinfunction "1_1") (pintype "passive"))
      (node (ref "D4") (pin "4") (pinfunction "C3_4") (pintype "passive"))
      (node (ref "J2") (pin "11") (pinfunction "11_11") (pintype "bidirectional"))
      (node (ref "J5") (pin "11") (pinfunction "11_11") (pintype "bidirectional"))
      (node (ref "R19") (pin "2") (pinfunction "2_2") (pintype "passive"))
      (node (ref "R3") (pin "2") (pinfunction "2_2") (pintype "passive"))
      (node (ref "R4") (pin "2") (pinfunction "2_2") (pintype "passive"))
      (node (ref "R40") (pin "2") (pinfunction "2_2") (pintype "passive"))
      (node (ref "R43") (pin "2") (pinfunction "2_2") (pintype "passive"))
      (node (ref "R45") (pin "2") (pinfunction "2_2") (pintype "passive"))
      (node (ref "R47") (pin "2") (pinfunction "2_2") (pintype "passive"))
      (node (ref "R49") (pin "2") (pinfunction "2_2") (pintype "passive"))
      (node (ref "R54") (pin "2") (pinfunction "2_2") (pintype "passive"))
      (node (ref "R57") (pin "2") (pinfunction "2_2") (pintype "passive"))
      (node (ref "R58") (pin "2") (pinfunction "2_2") (pintype "passive"))
      (node (ref "R59") (pin "2") (pinfunction "2_2") (pintype "passive"))
      (node (ref "R70") (pin "2") (pinfunction "2_2") (pintype "passive"))
      (node (ref "R71") (pin "2") (pinfunction "2_2") (pintype "passive"))
      (node (ref "R72") (pin "2") (pinfunction "2_2") (pintype "passive"))
      (node (ref "SD") (pin "4") (pinfunction "VDD_4") (pintype "bidirectional"))
      (node (ref "U4") (pin "5") (pinfunction "VOUT_5") (pintype "bidirectional"))
      (node (ref "U6") (pin "2") (pinfunction "3V3_2") (pintype "bidirectional"))
      (node (ref "U7") (pin "10") (pinfunction "V3_10") (pintype "bidirectional"))
      (node (ref "U7") (pin "7") (pinfunction "VCC_7") (pintype "bidirectional"))
    )
    (net (code "2") (name "/ANT") (class "Default")
      (node (ref "C42") (pin "2") (pinfunction "2_2") (pintype "passive"))
      (node (ref "R39") (pin "1") (pinfunction "1_1") (pintype "passive"))
      (node (ref "U5") (pin "60") (pinfunction "RF_ANT_60") (pintype "bidirectional"))
    )
    (net (code "3") (name "/BOOT") (class "Default")
      (node (ref "BOOT") (pin "2") (pinfunction "2_2") (pintype "passive"))
      (node (ref "U5") (pin "6") (pinfunction "USB_BOOT_6") (pintype "bidirectional"))
    )
    (net (code "4") (name "/DTR") (class "Default")
      (node (ref "Q11") (pin "2") (pinfunction "E_2") (pintype "passive"))
      (node (ref "R63") (pin "2") (pinfunction "2_2") (pintype "passive"))
      (node (ref "U7") (pin "4") (pinfunction "DTR#_4") (pintype "bidirectional"))
    )
    (net (code "5") (name "/EAR_N") (class "Default")
      (node (ref "FB2") (pin "2") (pinfunction "2_2") (pintype "passive"))
      (node (ref "U5") (pin "41") (pinfunction "EAR_N_41") (pintype "bidirectional"))
    )
    (net (code "6") (name "/EAR_P") (class "Default")
      (node (ref "FB1") (pin "1") (pinfunction "1_1") (pintype "passive"))
      (node (ref "U5") (pin "40") (pinfunction "EAR_P_40") (pintype "bidirectional"))
    )
    (net (code "7") (name "/GNSS_PWR_EN") (class "Default")
      (node (ref "U5") (pin "20") (pinfunction "MK_IN_3_20") (pintype "bidirectional"))
      (node (ref "U5") (pin "98") (pinfunction "NC_98") (pintype "bidirectional"))
    )
    (net (code "8") (name "/IO0") (class "Default")
      (node (ref "FLASH") (pin "2") (pinfunction "2_2") (pintype "passive"))
      (node (ref "Q11") (pin "3") (pinfunction "C_3") (pintype "passive"))
      (node (ref "R59") (pin "1") (pinfunction "1_1") (pintype "passive"))
      (node (ref "U6") (pin "27") (pinfunction "IO0_27") (pintype "bidirectional"))
    )
    (net (code "9") (name "/IO1") (class "Default")
      (node (ref "J2") (pin "1") (pinfunction "1_1") (pintype "bidirectional"))
      (node (ref "U6") (pin "39") (pinfunction "IO1_39") (pintype "bidirectional"))
    )
    (net (code "10") (name "/IO2") (class "Default")
      (node (ref "J2") (pin "2") (pinfunction "2_2") (pintype "bidirectional"))
      (node (ref "U6") (pin "38") (pinfunction "IO2_38") (pintype "bidirectional"))
    )
    (net (code "11") (name "/IO3") (class "Default")
      (node (ref "C1") (pin "1") (pinfunction "1_1") (pintype "passive"))
      (node (ref "J5") (pin "10") (pinfunction "10_10") (pintype "bidirectional"))
      (node (ref "R1") (pin "1") (pinfunction "1_1") (pintype "passive"))
      (node (ref "R2") (pin "2") (pinfunction "2_2") (pintype "passive"))
      (node (ref "U6") (pin "15") (pinfunction "IO3_15") (pintype "bidirectional"))
    )
    (net (code "12") (name "/IO4") (class "Default")
      (node (ref "R35") (pin "2") (pinfunction "2_2") (pintype "passive"))
      (node (ref "U6") (pin "4") (pinfunction "IO4_4") (pintype "bidirectional"))
    )
    (net (code "13") (name "/IO5") (class "Default")
      (node (ref "R31") (pin "2") (pinfunction "2_2") (pintype "passive"))
      (node (ref "U6") (pin "5") (pinfunction "IO5_5") (pintype "bidirectional"))
    )
    (net (code "14") (name "/IO6") (class "Default")
      (node (ref "Q8") (pin "3") (pinfunction "D_3") (pintype "passive"))
      (node (ref "R47") (pin "1") (pinfunction "1_1") (pintype "passive"))
      (node (ref "U6") (pin "6") (pinfunction "IO6_6") (pintype "bidirectional"))
    )
    (net (code "15") (name "/IO7") (class "Default")
      (node (ref "Q9") (pin "3") (pinfunction "D_3") (pintype "passive"))
      (node (ref "R49") (pin "1") (pinfunction "1_1") (pintype "passive"))
      (node (ref "U6") (pin "7") (pinfunction "IO7_7") (pintype "bidirectional"))
    )
    (net (code "16") (name "/IO8") (class "Default")
      (node (ref "J5") (pin "9") (pinfunction "9_9") (pintype "bidirectional"))
      (node (ref "U6") (pin "12") (pinfunction "IO8_12") (pintype "bidirectional"))
    )
    (net (code "17") (name "/IO9") (class "Default")
      (node (ref "J5") (pin "3") (pinfunction "3_3") (pintype "bidirectional"))
      (node (ref "U6") (pin "17") (pinfunction "IO9_17") (pintype "bidirectional"))
    )
    (net (code "18") (name "/IO10") (class "Default")
      (node (ref "R73") (pin "1") (pinfunction "1_1") (pintype "passive"))
      (node (ref "U6") (pin "18") (pinfunction "IO10_18") (pintype "bidirectional"))
    )
    (net (code "19") (name "/IO11{slash}MOSI") (class "Default")
      (node (ref "D4") (pin "3") (pinfunction "C2_3") (pintype "passive"))
      (node (ref "R4") (pin "1") (pinfunction "1_1") (pintype "passive"))
      (node (ref "SD") (pin "3") (pinfunction "DI_3") (pintype "bidirectional"))
      (node (ref "U6") (pin "19") (pinfunction "IO11_19") (pintype "bidirectional"))
    )
    (net (code "20") (name "/IO12{slash}SCLK") (class "Default")
      (node (ref "D4") (pin "5") (pinfunction "C4_5") (pintype "passive"))
      (node (ref "R3") (pin "1") (pinfunction "1_1") (pintype "passive"))
      (node (ref "SD") (pin "5") (pinfunction "SCLK_5") (pintype "bidirectional"))
      (node (ref "U6") (pin "20") (pinfunction "IO12_20") (pintype "bidirectional"))
    )
    (net (code "21") (name "/IO13{slash}MISO") (class "Default")
      (node (ref "D4") (pin "6") (pinfunction "C5_6") (pintype "passive"))
      (node (ref "R19") (pin "1") (pinfunction "1_1") (pintype "passive"))
      (node (ref "SD") (pin "7") (pinfunction "DO_7") (pintype "bidirectional"))
      (node (ref "U6") (pin "21") (pinfunction "IO13_21") (pintype "bidirectional"))
    )
    (net (code "22") (name "/IO14") (class "Default")
      (node (ref "J5") (pin "2") (pinfunction "2_2") (pintype "bidirectional"))
      (node (ref "U6") (pin "22") (pinfunction "IO14_22") (pintype "bidirectional"))
    )
    (net (code "23") (name "/IO15") (class "Default")
      (node (ref "J5") (pin "5") (pinfunction "5_5") (pintype "bidirectional"))
      (node (ref "U6") (pin "8") (pinfunction "IO15_8") (pintype "bidirectional"))
    )
    (net (code "24") (name "/IO16") (class "Default")
      (node (ref "J5") (pin "6") (pinfunction "6_6") (pintype "bidirectional"))
      (node (ref "U6") (pin "9") (pinfunction "IO16_9") (pintype "bidirectional"))
    )
    (net (code "25") (name "/IO17{slash}I2C_SDA") (class "Default")
      (node (ref "J5") (pin "7") (pinfunction "7_7") (pintype "bidirectional"))
      (node (ref "R58") (pin "1") (pinfunction "1_1") (pintype "passive"))
      (node (ref "U6") (pin "10") (pinfunction "IO17_10") (pintype "bidirectional"))
    )
    (net (code "26") (name "/IO18{slash}I2C_SCL") (class "Default")
      (node (ref "J5") (pin "8") (pinfunction "8_8") (pintype "bidirectional"))
      (node (ref "R57") (pin "1") (pinfunction "1_1") (pintype "passive"))
      (node (ref "U6") (pin "11") (pinfunction "IO18_11") (pintype "bidirectional"))
    )
    (net (code "27") (name "/IO19") (class "Default")
      (node (ref "R55") (pin "2") (pinfunction "2_2") (pintype "passive"))
      (node (ref "U6") (pin "13") (pinfunction "IO19_13") (pintype "bidirectional"))
    )
    (net (code "28") (name "/IO20") (class "Default")
      (node (ref "R56") (pin "2") (pinfunction "2_2") (pintype "passive"))
      (node (ref "U6") (pin "14") (pinfunction "IO20_14") (pintype "bidirectional"))
    )
    (net (code "29") (name "/IO21") (class "Default")
      (node (ref "U6") (pin "23") (pinfunction "IO21_23") (pintype "bidirectional"))
    )
    (net (code "30") (name "/IO38") (class "Default")
      (node (ref "J2") (pin "9") (pinfunction "9_9") (pintype "bidirectional"))
      (node (ref "U6") (pin "31") (pinfunction "IO38_31") (pintype "bidirectional"))
    )
    (net (code "31") (name "/IO39") (class "Default")
      (node (ref "J2") (pin "8") (pinfunction "8_8") (pintype "bidirectional"))
      (node (ref "U6") (pin "32") (pinfunction "IO39_32") (pintype "bidirectional"))
    )
    (net (code "32") (name "/IO40") (class "Default")
      (node (ref "J2") (pin "7") (pinfunction "7_7") (pintype "bidirectional"))
      (node (ref "U6") (pin "33") (pinfunction "IO40_33") (pintype "bidirectional"))
    )
    (net (code "33") (name "/IO41") (class "Default")
      (node (ref "J2") (pin "6") (pinfunction "6_6") (pintype "bidirectional"))
      (node (ref "U6") (pin "34") (pinfunction "IO41_34") (pintype "bidirectional"))
    )
    (net (code "34") (name "/IO42") (class "Default")
      (node (ref "J2") (pin "5") (pinfunction "5_5") (pintype "bidirectional"))
      (node (ref "U6") (pin "35") (pinfunction "IO42_35") (pintype "bidirectional"))
    )
    (net (code "35") (name "/IO45") (class "Default")
      (node (ref "J5") (pin "1") (pinfunction "1_1") (pintype "bidirectional"))
      (node (ref "U6") (pin "26") (pinfunction "IO45_26") (pintype "bidirectional"))
    )
    (net (code "36") (name "/IO46") (class "Default")
      (node (ref "J5") (pin "4") (pinfunction "4_4") (pintype "bidirectional"))
      (node (ref "U6") (pin "16") (pinfunction "IO46_16") (pintype "bidirectional"))
    )
    (net (code "37") (name "/IO47") (class "Default")
      (node (ref "Q5") (pin "3") (pinfunction "D_3") (pintype "passive"))
      (node (ref "R43") (pin "1") (pinfunction "1_1") (pintype "passive"))
      (node (ref "U6") (pin "24") (pinfunction "IO33_24") (pintype "bidirectional"))
    )
    (net (code "38") (name "/IO48") (class "Default")
      (node (ref "Q7") (pin "3") (pinfunction "D_3") (pintype "passive"))
      (node (ref "R45") (pin "1") (pinfunction "1_1") (pintype "passive"))
      (node (ref "U6") (pin "25") (pinfunction "IO34_25") (pintype "bidirectional"))
    )
    (net (code "39") (name "/LTE_DTR") (class "Default")
      (node (ref "Q9") (pin "2") (pinfunction "S_2") (pintype "passive"))
      (node (ref "R50") (pin "1") (pinfunction "1_1") (pintype "passive"))
      (node (ref "U5") (pin "3") (pinfunction "DTR_3") (pintype "bidirectional"))
    )
    (net (code "40") (name "/LTE_RI") (class "Default")
      (node (ref "Q8") (pin "2") (pinfunction "S_2") (pintype "passive"))
      (node (ref "R48") (pin "1") (pinfunction "1_1") (pintype "passive"))
      (node (ref "U5") (pin "4") (pinfunction "RI_4") (pintype "bidirectional"))
    )
    (net (code "41") (name "/LTE_RXD") (class "Default")
      (node (ref "Q7") (pin "2") (pinfunction "S_2") (pintype "passive"))
      (node (ref "R46") (pin "1") (pinfunction "1_1") (pintype "passive"))
      (node (ref "U5") (pin "10") (pinfunction "RXD_10") (pintype "bidirectional"))
    )
    (net (code "42") (name "/LTE_TXD") (class "Default")
      (node (ref "Q5") (pin "2") (pinfunction "S_2") (pintype "passive"))
      (node (ref "R44") (pin "1") (pinfunction "1_1") (pintype "passive"))
      (node (ref "U5") (pin "9") (pinfunction "TXD_9") (pintype "bidirectional"))
    )
    (net (code "43") (name "/MF_GNSS_RXD") (class "Default")
      (node (ref "R52") (pin "2") (pinfunction "2_2") (pintype "passive"))
      (node (ref "U5") (pin "49") (pinfunction "UART3_RXD_49") (pintype "bidirectional"))
    )
    (net (code "44") (name "/MF_GNSS_TXD") (class "Default")
      (node (ref "R53") (pin "2") (pinfunction "2_2") (pintype "passive"))
      (node (ref "U5") (pin "50") (pinfunction "UART3_TXD_50") (pintype "bidirectional"))
    )
    (net (code "45") (name "/MIC_N") (class "Default")
      (node (ref "FB4") (pin "1") (pinfunction "1_1") (pintype "passive"))
      (node (ref "R33") (pin "1") (pinfunction "1_1") (pintype "passive"))
      (node (ref "U5") (pin "43") (pinfunction "MIC_N_43") (pintype "bidirectional"))
    )
    (net (code "46") (name "/MIC_P") (class "Default")
      (node (ref "FB3") (pin "1") (pinfunction "1_1") (pintype "passive"))
      (node (ref "U5") (pin "42") (pinfunction "MIC_P_42") (pintype "bidirectional"))
    )
    (net (code "47") (name "/NETLED") (class "Default")
      (node (ref "R16") (pin "2") (pinfunction "2_2") (pintype "passive"))
      (node (ref "U5") (pin "52") (pinfunction "NETLIGHT_52") (pintype "bidirectional"))
    )
    (net (code "48") (name "/NRST") (class "Default")
      (node (ref "D12") (pin "-") (pinfunction "-_-") (pintype "passive"))
      (node (ref "Q1") (pin "3") (pinfunction "D_3") (pintype "passive"))
      (node (ref "U5") (pin "16") (pinfunction "RESET_16") (pintype "bidirectional"))
    )
    (net (code "49") (name "/PWRKEY") (class "Default")
      (node (ref "C27") (pin "2") (pinfunction "2_2") (pintype "passive"))
      (node (ref "PWK") (pin "2") (pinfunction "2_2") (pintype "passive"))
      (node (ref "Q3") (pin "3") (pinfunction "D_3") (pintype "passive"))
      (node (ref "U5") (pin "1") (pinfunction "PWRKEY_1") (pintype "bidirectional"))
    )
    (net (code "50") (name "/RESET") (class "Default")
      (node (ref "C39") (pin "1") (pinfunction "1_1") (pintype "passive"))
      (node (ref "Q10") (pin "3") (pinfunction "C_3") (pintype "passive"))
      (node (ref "R54") (pin "1") (pinfunction "1_1") (pintype "passive"))
      (node (ref "RST") (pin "2") (pinfunction "2_2") (pintype "passive"))
      (node (ref "U6") (pin "3") (pinfunction "EN_3") (pintype "bidirectional"))
    )
    (net (code "51") (name "/RTS") (class "Default")
      (node (ref "Q10") (pin "2") (pinfunction "E_2") (pintype "passive"))
      (node (ref "R62") (pin "2") (pinfunction "2_2") (pintype "passive"))
      (node (ref "U7") (pin "6") (pinfunction "RTS#_6") (pintype "bidirectional"))
    )
    (net (code "52") (name "/RXD{slash}IO44") (class "Default")
      (node (ref "J2") (pin "4") (pinfunction "4_4") (pintype "bidirectional"))
      (node (ref "R68") (pin "1") (pinfunction "1_1") (pintype "passive"))
      (node (ref "U6") (pin "36") (pinfunction "RXD0_36") (pintype "bidirectional"))
    )
    (net (code "53") (name "/SD_CS") (class "Default")
      (node (ref "D4") (pin "1") (pinfunction "C1_1") (pintype "passive"))
      (node (ref "R71") (pin "1") (pinfunction "1_1") (pintype "passive"))
      (node (ref "R73") (pin "2") (pinfunction "2_2") (pintype "passive"))
      (node (ref "SD") (pin "2") (pinfunction "CS_2") (pintype "bidirectional"))
    )
    (net (code "54") (name "/SIM_CLK") (class "Default")
      (node (ref "C35") (pin "2") (pinfunction "2_2") (pintype "passive"))
      (node (ref "D10") (pin "4") (pinfunction "C3_4") (pintype "passive"))
      (node (ref "R23") (pin "2") (pinfunction "2_2") (pintype "passive"))
      (node (ref "SIM") (pin "3") (pinfunction "CLK_3") (pintype "bidirectional"))
    )
    (net (code "55") (name "/SIM_DATA") (class "Default")
      (node (ref "C36") (pin "2") (pinfunction "2_2") (pintype "passive"))
      (node (ref "D10") (pin "3") (pinfunction "C2_3") (pintype "passive"))
      (node (ref "R22") (pin "2") (pinfunction "2_2") (pintype "passive"))
      (node (ref "SIM") (pin "7") (pinfunction "I/O_7") (pintype "bidirectional"))
    )
    (net (code "56") (name "/SIM_RST") (class "Default")
      (node (ref "C34") (pin "2") (pinfunction "2_2") (pintype "passive"))
      (node (ref "D10") (pin "5") (pinfunction "C4_5") (pintype "passive"))
      (node (ref "R24") (pin "2") (pinfunction "2_2") (pintype "passive"))
      (node (ref "SIM") (pin "2") (pinfunction "RST_2") (pintype "bidirectional"))
    )
    (net (code "57") (name "/SIM_VDD") (class "Default")
      (node (ref "C21") (pin "2") (pinfunction "2_2") (pintype "passive"))
      (node (ref "C52") (pin "2") (pinfunction "2_2") (pintype "passive"))
      (node (ref "D10") (pin "6") (pinfunction "C5_6") (pintype "passive"))
      (node (ref "SIM") (pin "1") (pinfunction "VCC_1") (pintype "bidirectional"))
      (node (ref "U5") (pin "30") (pinfunction "USIM1_VDD_30") (pintype "bidirectional"))
    )
    (net (code "58") (name "/STATUS") (class "Default")
      (node (ref "R41") (pin "2") (pinfunction "2_2") (pintype "passive"))
      (node (ref "U5") (pin "66") (pinfunction "STATUS_66") (pintype "bidirectional"))
    )
    (net (code "59") (name "/TXD{slash}IO43") (class "Default")
      (node (ref "J2") (pin "3") (pinfunction "3_3") (pintype "bidirectional"))
      (node (ref "R69") (pin "1") (pinfunction "1_1") (pintype "passive"))
      (node (ref "U6") (pin "37") (pinfunction "TXD0_37") (pintype "bidirectional"))
    )
    (net (code "60") (name "/UART_LOG_RX") (class "Default")
      (node (ref "RX") (pin "T") (pinfunction "T_T") (pintype "bidirectional"))
      (node (ref "U5") (pin "22") (pinfunction "UART_LOG_RX_22") (pintype "bidirectional"))
    )
    (net (code "61") (name "/UART_LOG_TX") (class "Default")
      (node (ref "TX") (pin "T") (pinfunction "T_T") (pintype "bidirectional"))
      (node (ref "U5") (pin "23") (pinfunction "UART_LOG_TX_23") (pintype "bidirectional"))
    )
    (net (code "62") (name "/USB_D+") (class "Default")
      (node (ref "R56") (pin "1") (pinfunction "1_1") (pintype "passive"))
      (node (ref "USB-NATIVE") (pin "A6") (pinfunction "D+_A6") (pintype "bidirectional"))
      (node (ref "USB-NATIVE") (pin "B6") (pinfunction "D+_B6") (pintype "bidirectional"))
    )
    (net (code "63") (name "/USB_D-") (class "Default")
      (node (ref "R55") (pin "1") (pinfunction "1_1") (pintype "passive"))
      (node (ref "USB-NATIVE") (pin "A7") (pinfunction "D-_A7") (pintype "bidirectional"))
      (node (ref "USB-NATIVE") (pin "B7") (pinfunction "D-_B7") (pintype "bidirectional"))
    )
    (net (code "64") (name "/USB_DN") (class "Default")
      (node (ref "R29") (pin "1") (pinfunction "1_1") (pintype "passive"))
      (node (ref "U5") (pin "28") (pinfunction "USB_DM_28") (pintype "bidirectional"))
    )
    (net (code "65") (name "/USB_DP") (class "Default")
      (node (ref "R28") (pin "1") (pinfunction "1_1") (pintype "passive"))
      (node (ref "U5") (pin "27") (pinfunction "USB_DP_27") (pintype "bidirectional"))
    )
    (net (code "66") (name "/V4D2") (class "Default")
      (node (ref "C3") (pin "2") (pinfunction "2_2") (pintype "passive"))
      (node (ref "C41") (pin "2") (pinfunction "2_2") (pintype "passive"))
      (node (ref "C60") (pin "2") (pinfunction "2_2") (pintype "passive"))
      (node (ref "C61") (pin "2") (pinfunction "2_2") (pintype "passive"))
      (node (ref "D11") (pin "A") (pinfunction "A_A") (pintype "passive"))
      (node (ref "L2") (pin "2") (pinfunction "2_2") (pintype "passive"))
      (node (ref "Q2") (pin "1") (pinfunction "G_1") (pintype "passive"))
      (node (ref "R15") (pin "1") (pinfunction "1_1") (pintype "passive"))
      (node (ref "R75") (pin "2") (pinfunction "2_2") (pintype "passive"))
      (node (ref "U2") (pin "5") (pinfunction "OUT_5") (pintype "bidirectional"))
    )
    (net (code "67") (name "/VBAT-") (class "Default")
      (node (ref "BAT") (pin "1") (pinfunction "1_1") (pintype "bidirectional"))
      (node (ref "C25") (pin "1") (pinfunction "1_1") (pintype "passive"))
      (node (ref "J3") (pin "2") (pinfunction "2_2") (pintype "passive"))
      (node (ref "R10") (pin "2") (pinfunction "2_2") (pintype "passive"))
      (node (ref "U1") (pin "3") (pinfunction "S2_3") (pintype "bidirectional"))
      (node (ref "U1") (pin "6") (pinfunction "VSS_6") (pintype "bidirectional"))
    )
    (net (code "68") (name "/VBAT_ADC") (class "Default")
      (node (ref "C2") (pin "1") (pinfunction "1_1") (pintype "passive"))
      (node (ref "R5") (pin "1") (pinfunction "1_1") (pintype "passive"))
      (node (ref "R7") (pin "2") (pinfunction "2_2") (pintype "passive"))
      (node (ref "U5") (pin "51") (pinfunction "VBAT_ADC_51") (pintype "bidirectional"))
    )
    (net (code "69") (name "/VBAT_IN") (class "Default")
      (node (ref "C29") (pin "1") (pinfunction "1_1") (pintype "passive"))
      (node (ref "C38") (pin "1") (pinfunction "1_1") (pintype "passive"))
      (node (ref "D2") (pin "A") (pinfunction "A_A") (pintype "passive"))
      (node (ref "Q2") (pin "3") (pinfunction "D_3") (pintype "passive"))
      (node (ref "R5") (pin "2") (pinfunction "2_2") (pintype "passive"))
      (node (ref "SW1") (pin "CH1A") (pinfunction "CH1A_CH1A") (pintype "bidirectional"))
    )
    (net (code "70") (name "/VIN") (class "Default")
      (node (ref "C10") (pin "2") (pinfunction "2_2") (pintype "passive"))
      (node (ref "C17") (pin "2") (pinfunction "2_2") (pintype "passive"))
      (node (ref "D11") (pin "C") (pinfunction "C_C") (pintype "passive"))
      (node (ref "D2") (pin "C") (pinfunction "C_C") (pintype "passive"))
      (node (ref "Q2") (pin "2") (pinfunction "S_2") (pintype "passive"))
      (node (ref "R6") (pin "2") (pinfunction "2_2") (pintype "passive"))
      (node (ref "R78") (pin "2") (pinfunction "2_2") (pintype "passive"))
      (node (ref "U4") (pin "1") (pinfunction "VIN_1") (pintype "bidirectional"))
      (node (ref "U4") (pin "3") (pinfunction "EN_3") (pintype "bidirectional"))
    )
    (net (code "71") (name "/VSYS") (class "Default")
      (node (ref "C62") (pin "2") (pinfunction "2_2") (pintype "passive"))
      (node (ref "C63") (pin "2") (pinfunction "2_2") (pintype "passive"))
      (node (ref "C64") (pin "2") (pinfunction "2_2") (pintype "passive"))
      (node (ref "R76") (pin "2") (pinfunction "2_2") (pintype "passive"))
      (node (ref "R77") (pin "2") (pinfunction "2_2") (pintype "passive"))
      (node (ref "SW1") (pin "CH2A") (pinfunction "CH2A_CH2A") (pintype "bidirectional"))
      (node (ref "U2") (pin "2") (pinfunction "VIN_2") (pintype "bidirectional"))
    )
    (net (code "72") (name "/VUSB") (class "Default")
      (node (ref "C12") (pin "1") (pinfunction "1_1") (pintype "passive"))
      (node (ref "C15") (pin "1") (pinfunction "1_1") (pintype "passive"))
      (node (ref "D5") (pin "A") (pinfunction "A_A") (pintype "passive"))
      (node (ref "U5") (pin "24") (pinfunction "VBUS_24") (pintype "bidirectional"))
      (node (ref "USB-LTE") (pin "VBUS1") (pinfunction "VBUS_VBUS1") (pintype "bidirectional"))
      (node (ref "USB-LTE") (pin "VBUS2") (pinfunction "VBUS_VBUS2") (pintype "bidirectional"))
    )
    (net (code "73") (name "1.8V") (class "Default")
      (node (ref "1V8") (pin "T") (pinfunction "T_T") (pintype "bidirectional"))
      (node (ref "C32") (pin "2") (pinfunction "2_2") (pintype "passive"))
      (node (ref "C33") (pin "2") (pinfunction "2_2") (pintype "passive"))
      (node (ref "D6") (pin "+") (pinfunction "+_+") (pintype "passive"))
      (node (ref "Q5") (pin "1") (pinfunction "G_1") (pintype "passive"))
      (node (ref "Q7") (pin "1") (pinfunction "G_1") (pintype "passive"))
      (node (ref "Q8") (pin "1") (pinfunction "G_1") (pintype "passive"))
      (node (ref "Q9") (pin "1") (pinfunction "G_1") (pintype "passive"))
      (node (ref "R44") (pin "2") (pinfunction "2_2") (pintype "passive"))
      (node (ref "R46") (pin "2") (pinfunction "2_2") (pintype "passive"))
      (node (ref "R48") (pin "2") (pinfunction "2_2") (pintype "passive"))
      (node (ref "R50") (pin "2") (pinfunction "2_2") (pintype "passive"))
      (node (ref "U5") (pin "15") (pinfunction "VDD_EXT_15") (pintype "bidirectional"))
      (node (ref "U5") (pin "97") (pinfunction "NC_97") (pintype "bidirectional"))
    )
    (net (code "74") (name "5V") (class "Default")
      (node (ref "C13") (pin "1") (pinfunction "1_1") (pintype "passive"))
      (node (ref "CHRG") (pin "A") (pinfunction "A_A") (pintype "passive"))
      (node (ref "D14") (pin "-") (pinfunction "-_-") (pintype "passive"))
      (node (ref "D3") (pin "C") (pinfunction "C_C") (pintype "passive"))
      (node (ref "D5") (pin "C") (pinfunction "C_C") (pintype "passive"))
      (node (ref "D9") (pin "-") (pinfunction "-_-") (pintype "passive"))
      (node (ref "DONE") (pin "A") (pinfunction "A_A") (pintype "passive"))
      (node (ref "J2") (pin "13") (pinfunction "13_13") (pintype "bidirectional"))
      (node (ref "SW1") (pin "COM2") (pinfunction "COM2_COM2") (pintype "bidirectional"))
      (node (ref "U3") (pin "4") (pinfunction "VIN_4") (pintype "bidirectional"))
      (node (ref "U3") (pin "8") (pinfunction "CE_8") (pintype "bidirectional"))
      (node (ref "USB-NATIVE") (pin "VBUS1") (pinfunction "VBUS_VBUS1") (pintype "bidirectional"))
      (node (ref "USB-NATIVE") (pin "VBUS2") (pinfunction "VBUS_VBUS2") (pintype "bidirectional"))
    )
    (net (code "75") (name "AGND") (class "Default")
      (node (ref "C14") (pin "1") (pinfunction "1_1") (pintype "passive"))
      (node (ref "C16") (pin "1") (pinfunction "1_1") (pintype "passive"))
      (node (ref "C20") (pin "1") (pinfunction "1_1") (pintype "passive"))
      (node (ref "C4") (pin "1") (pinfunction "1_1") (pintype "passive"))
      (node (ref "C56") (pin "2") (pinfunction "2_2") (pintype "passive"))
      (node (ref "C57") (pin "2") (pinfunction "2_2") (pintype "passive"))
      (node (ref "C79") (pin "1") (pinfunction "1_1") (pintype "passive"))
      (node (ref "C80") (pin "2") (pinfunction "2_2") (pintype "passive"))
      (node (ref "C82") (pin "2") (pinfunction "2_2") (pintype "passive"))
      (node (ref "C83") (pin "1") (pinfunction "1_1") (pintype "passive"))
      (node (ref "FB5") (pin "1") (pinfunction "1_1") (pintype "passive"))
      (node (ref "R33") (pin "2") (pinfunction "2_2") (pintype "passive"))
    )
    (net (code "76") (name "D+") (class "Default")
      (node (ref "U7") (pin "1") (pinfunction "UD+_1") (pintype "bidirectional"))
      (node (ref "USB-TTL") (pin "A6") (pinfunction "D+_A6") (pintype "bidirectional"))
      (node (ref "USB-TTL") (pin "B6") (pinfunction "D+_B6") (pintype "bidirectional"))
    )
    (net (code "77") (name "D-") (class "Default")
      (node (ref "U7") (pin "2") (pinfunction "UD-_2") (pintype "bidirectional"))
      (node (ref "USB-TTL") (pin "A7") (pinfunction "D-_A7") (pintype "bidirectional"))
      (node (ref "USB-TTL") (pin "B7") (pinfunction "D-_B7") (pintype "bidirectional"))
    )
    (net (code "78") (name "GND") (class "Default")
      (node (ref "C1") (pin "2") (pinfunction "2_2") (pintype "passive"))
      (node (ref "C10") (pin "1") (pinfunction "1_1") (pintype "passive"))
      (node (ref "C11") (pin "1") (pinfunction "1_1") (pintype "passive"))
      (node (ref "C12") (pin "2") (pinfunction "2_2") (pintype "passive"))
      (node (ref "C13") (pin "2") (pinfunction "2_2") (pintype "passive"))
      (node (ref "C15") (pin "2") (pinfunction "2_2") (pintype "passive"))
      (node (ref "C17") (pin "1") (pinfunction "1_1") (pintype "passive"))
      (node (ref "C18") (pin "1") (pinfunction "1_1") (pintype "passive"))
      (node (ref "C19") (pin "1") (pinfunction "1_1") (pintype "passive"))
      (node (ref "C2") (pin "2") (pinfunction "2_2") (pintype "passive"))
      (node (ref "C21") (pin "1") (pinfunction "1_1") (pintype "passive"))
      (node (ref "C22") (pin "1") (pinfunction "1_1") (pintype "passive"))
      (node (ref "C23") (pin "1") (pinfunction "1_1") (pintype "passive"))
      (node (ref "C24") (pin "1") (pinfunction "1_1") (pintype "passive"))
      (node (ref "C26") (pin "C") (pinfunction "-_C") (pintype "passive"))
      (node (ref "C27") (pin "1") (pinfunction "1_1") (pintype "passive"))
      (node (ref "C29") (pin "2") (pinfunction "2_2") (pintype "passive"))
      (node (ref "C3") (pin "1") (pinfunction "1_1") (pintype "passive"))
      (node (ref "C30") (pin "1") (pinfunction "1_1") (pintype "passive"))
      (node (ref "C31") (pin "1") (pinfunction "1_1") (pintype "passive"))
      (node (ref "C32") (pin "1") (pinfunction "1_1") (pintype "passive"))
      (node (ref "C33") (pin "1") (pinfunction "1_1") (pintype "passive"))
      (node (ref "C34") (pin "1") (pinfunction "1_1") (pintype "passive"))
      (node (ref "C35") (pin "1") (pinfunction "1_1") (pintype "passive"))
      (node (ref "C36") (pin "1") (pinfunction "1_1") (pintype "passive"))
      (node (ref "C38") (pin "2") (pinfunction "2_2") (pintype "passive"))
      (node (ref "C39") (pin "2") (pinfunction "2_2") (pintype "passive"))
      (node (ref "C40") (pin "1") (pinfunction "1_1") (pintype "passive"))
      (node (ref "C41") (pin "1") (pinfunction "1_1") (pintype "passive"))
      (node (ref "C42") (pin "1") (pinfunction "1_1") (pintype "passive"))
      (node (ref "C43") (pin "1") (pinfunction "1_1") (pintype "passive"))
      (node (ref "C44") (pin "2") (pinfunction "2_2") (pintype "passive"))
      (node (ref "C46") (pin "1") (pinfunction "1_1") (pintype "passive"))
      (node (ref "C47") (pin "1") (pinfunction "1_1") (pintype "passive"))
      (node (ref "C48") (pin "C") (pinfunction "-_C") (pintype "passive"))
      (node (ref "C49") (pin "1") (pinfunction "1_1") (pintype "passive"))
      (node (ref "C5") (pin "1") (pinfunction "1_1") (pintype "passive"))
      (node (ref "C50") (pin "1") (pinfunction "1_1") (pintype "passive"))
      (node (ref "C51") (pin "1") (pinfunction "1_1") (pintype "passive"))
      (node (ref "C52") (pin "1") (pinfunction "1_1") (pintype "passive"))
      (node (ref "C53") (pin "1") (pinfunction "1_1") (pintype "passive"))
      (node (ref "C54") (pin "1") (pinfunction "1_1") (pintype "passive"))
      (node (ref "C58") (pin "1") (pinfunction "1_1") (pintype "passive"))
      (node (ref "C59") (pin "1") (pinfunction "1_1") (pintype "passive"))
      (node (ref "C6") (pin "1") (pinfunction "1_1") (pintype "passive"))
      (node (ref "C60") (pin "1") (pinfunction "1_1") (pintype "passive"))
      (node (ref "C62") (pin "1") (pinfunction "1_1") (pintype "passive"))
      (node (ref "C63") (pin "1") (pinfunction "1_1") (pintype "passive"))
      (node (ref "C64") (pin "1") (pinfunction "1_1") (pintype "passive"))
      (node (ref "C7") (pin "2") (pinfunction "2_2") (pintype "passive"))
      (node (ref "C8") (pin "2") (pinfunction "2_2") (pintype "passive"))
      (node (ref "D10") (pin "2") (pinfunction "A_2") (pintype "passive"))
      (node (ref "D12") (pin "+") (pinfunction "+_+") (pintype "passive"))
      (node (ref "D13") (pin "+") (pinfunction "+_+") (pintype "passive"))
      (node (ref "D14") (pin "+") (pinfunction "+_+") (pintype "passive"))
      (node (ref "D4") (pin "2") (pinfunction "A_2") (pintype "passive"))
      (node (ref "D7") (pin "+") (pinfunction "+_+") (pintype "passive"))
      (node (ref "D8") (pin "A") (pinfunction "A_A") (pintype "passive"))
      (node (ref "D9") (pin "+") (pinfunction "+_+") (pintype "passive"))
      (node (ref "FB5") (pin "2") (pinfunction "2_2") (pintype "passive"))
      (node (ref "FLASH") (pin "1") (pinfunction "1_1") (pintype "passive"))
      (node (ref "GND") (pin "T") (pinfunction "T_T") (pintype "bidirectional"))
      (node (ref "GPS") (pin "GND1") (pinfunction "GND1_GND1") (pintype "bidirectional"))
      (node (ref "GPS") (pin "GND2") (pinfunction "GND2_GND2") (pintype "bidirectional"))
      (node (ref "GPS") (pin "GND3") (pinfunction "GND3_GND3") (pintype "bidirectional"))
      (node (ref "J1") (pin "2") (pinfunction "2_2") (pintype "bidirectional"))
      (node (ref "J2") (pin "10") (pinfunction "10_10") (pintype "bidirectional"))
      (node (ref "J2") (pin "12") (pinfunction "12_12") (pintype "bidirectional"))
      (node (ref "J5") (pin "12") (pinfunction "12_12") (pintype "bidirectional"))
      (node (ref "LTE") (pin "GND1") (pinfunction "GND1_GND1") (pintype "bidirectional"))
      (node (ref "LTE") (pin "GND2") (pinfunction "GND2_GND2") (pintype "bidirectional"))
      (node (ref "LTE") (pin "GND3") (pinfunction "GND3_GND3") (pintype "bidirectional"))
      (node (ref "PWK") (pin "1") (pinfunction "1_1") (pintype "passive"))
      (node (ref "Q1") (pin "2") (pinfunction "S_2") (pintype "passive"))
      (node (ref "Q3") (pin "2") (pinfunction "S_2") (pintype "passive"))
      (node (ref "Q4") (pin "2") (pinfunction "S_2") (pintype "passive"))
      (node (ref "Q6") (pin "2") (pinfunction "S_2") (pintype "passive"))
      (node (ref "R10") (pin "1") (pinfunction "1_1") (pintype "passive"))
      (node (ref "R12") (pin "2") (pinfunction "2_2") (pintype "passive"))
      (node (ref "R14") (pin "1") (pinfunction "1_1") (pintype "passive"))
      (node (ref "R15") (pin "2") (pinfunction "2_2") (pintype "passive"))
      (node (ref "R2") (pin "1") (pinfunction "1_1") (pintype "passive"))
      (node (ref "R25") (pin "2") (pinfunction "2_2") (pintype "passive"))
      (node (ref "R26") (pin "1") (pinfunction "1_1") (pintype "passive"))
      (node (ref "R27") (pin "1") (pinfunction "1_1") (pintype "passive"))
      (node (ref "R30") (pin "2") (pinfunction "2_2") (pintype "passive"))
      (node (ref "R32") (pin "1") (pinfunction "1_1") (pintype "passive"))
      (node (ref "R34") (pin "2") (pinfunction "2_2") (pintype "passive"))
      (node (ref "R36") (pin "1") (pinfunction "1_1") (pintype "passive"))
      (node (ref "R42") (pin "1") (pinfunction "1_1") (pintype "passive"))
      (node (ref "R60") (pin "1") (pinfunction "1_1") (pintype "passive"))
      (node (ref "R61") (pin "1") (pinfunction "1_1") (pintype "passive"))
      (node (ref "R64") (pin "1") (pinfunction "1_1") (pintype "passive"))
      (node (ref "R67") (pin "1") (pinfunction "1_1") (pintype "passive"))
      (node (ref "R7") (pin "1") (pinfunction "1_1") (pintype "passive"))
      (node (ref "R74") (pin "1") (pinfunction "1_1") (pintype "passive"))
      (node (ref "R8") (pin "1") (pinfunction "1_1") (pintype "passive"))
      (node (ref "RST") (pin "1") (pinfunction "1_1") (pintype "passive"))
      (node (ref "SD") (pin "6") (pinfunction "VSS_6") (pintype "bidirectional"))
      (node (ref "SD") (pin "G1") (pinfunction "G1_G1") (pintype "bidirectional"))
      (node (ref "SD") (pin "G2") (pinfunction "G2_G2") (pintype "bidirectional"))
      (node (ref "SD") (pin "G3") (pinfunction "G3_G3") (pintype "bidirectional"))
      (node (ref "SD") (pin "G4") (pinfunction "G4_G4") (pintype "bidirectional"))
      (node (ref "SIM") (pin "5") (pinfunction "GND_5") (pintype "bidirectional"))
      (node (ref "U1") (pin "2") (pinfunction "S1_2") (pintype "bidirectional"))
      (node (ref "U2") (pin "4") (pinfunction "PGND_4") (pintype "bidirectional"))
      (node (ref "U2") (pin "6") (pinfunction "AGND_6") (pintype "bidirectional"))
      (node (ref "U3") (pin "1") (pinfunction "TEMP_1") (pintype "bidirectional"))
      (node (ref "U3") (pin "3") (pinfunction "GND_3") (pintype "bidirectional"))
      (node (ref "U3") (pin "9") (pinfunction "GND_9") (pintype "bidirectional"))
      (node (ref "U4") (pin "2") (pinfunction "GND_2") (pintype "bidirectional"))
      (node (ref "U5") (pin "17") (pinfunction "GND_17") (pintype "bidirectional"))
      (node (ref "U5") (pin "18") (pinfunction "GND_18") (pintype "bidirectional"))
      (node (ref "U5") (pin "2") (pinfunction "GND_2") (pintype "bidirectional"))
      (node (ref "U5") (pin "29") (pinfunction "GND_29") (pintype "bidirectional"))
      (node (ref "U5") (pin "39") (pinfunction "GND_39") (pintype "bidirectional"))
      (node (ref "U5") (pin "45") (pinfunction "GND_45") (pintype "bidirectional"))
      (node (ref "U5") (pin "46") (pinfunction "GND_46") (pintype "bidirectional"))
      (node (ref "U5") (pin "54") (pinfunction "GND_54") (pintype "bidirectional"))
      (node (ref "U5") (pin "58") (pinfunction "GND_58") (pintype "bidirectional"))
      (node (ref "U5") (pin "59") (pinfunction "GND_59") (pintype "bidirectional"))
      (node (ref "U5") (pin "61") (pinfunction "GND_61") (pintype "bidirectional"))
      (node (ref "U5") (pin "62") (pinfunction "GND_62") (pintype "bidirectional"))
      (node (ref "U5") (pin "63") (pinfunction "GND_63") (pintype "bidirectional"))
      (node (ref "U5") (pin "64") (pinfunction "GND_64") (pintype "bidirectional"))
      (node (ref "U5") (pin "65") (pinfunction "GND_65") (pintype "bidirectional"))
      (node (ref "U5") (pin "69") (pinfunction "GND_69") (pintype "bidirectional"))
      (node (ref "U5") (pin "70") (pinfunction "GND_70") (pintype "bidirectional"))
      (node (ref "U5") (pin "71") (pinfunction "GND_71") (pintype "bidirectional"))
      (node (ref "U5") (pin "72") (pinfunction "GND_72") (pintype "bidirectional"))
      (node (ref "U5") (pin "73") (pinfunction "GND_73") (pintype "bidirectional"))
      (node (ref "U5") (pin "74") (pinfunction "GND_74") (pintype "bidirectional"))
      (node (ref "U5") (pin "75") (pinfunction "GND_75") (pintype "bidirectional"))
      (node (ref "U5") (pin "76") (pinfunction "GND_76") (pintype "bidirectional"))
      (node (ref "U5") (pin "77") (pinfunction "GND_77") (pintype "bidirectional"))
      (node (ref "U5") (pin "78") (pinfunction "GND_78") (pintype "bidirectional"))
      (node (ref "U5") (pin "79") (pinfunction "GND_79") (pintype "bidirectional"))
      (node (ref "U5") (pin "80") (pinfunction "GND_80") (pintype "bidirectional"))
      (node (ref "U5") (pin "81") (pinfunction "GND_81") (pintype "bidirectional"))
      (node (ref "U5") (pin "82") (pinfunction "GND_82") (pintype "bidirectional"))
      (node (ref "U5") (pin "83") (pinfunction "GND_83") (pintype "bidirectional"))
      (node (ref "U5") (pin "84") (pinfunction "GND_84") (pintype "bidirectional"))
      (node (ref "U5") (pin "85") (pinfunction "GND_85") (pintype "bidirectional"))
      (node (ref "U5") (pin "86") (pinfunction "GND_86") (pintype "bidirectional"))
      (node (ref "U5") (pin "87") (pinfunction "GND_87") (pintype "bidirectional"))
      (node (ref "U5") (pin "88") (pinfunction "GND_88") (pintype "bidirectional"))
      (node (ref "U5") (pin "89") (pinfunction "GND_89") (pintype "bidirectional"))
      (node (ref "U5") (pin "91") (pinfunction "GND_91") (pintype "bidirectional"))
      (node (ref "U5") (pin "92") (pinfunction "GND_92") (pintype "bidirectional"))
      (node (ref "U5") (pin "94") (pinfunction "GND_94") (pintype "bidirectional"))
      (node (ref "U6") (pin "1") (pinfunction "GND_1") (pintype "bidirectional"))
      (node (ref "U6") (pin "40") (pinfunction "GND_40") (pintype "bidirectional"))
      (node (ref "U6") (pin "41") (pinfunction "EPAD_41") (pintype "bidirectional"))
      (node (ref "U7") (pin "3") (pinfunction "GND_3") (pintype "bidirectional"))
      (node (ref "U7") (pin "EP") (pinfunction "EP_EP") (pintype "bidirectional"))
      (node (ref "USB-LTE") (pin "GND") (pinfunction "GND_GND") (pintype "bidirectional"))
      (node (ref "USB-LTE") (pin "GND2") (pinfunction "GND_GND2") (pintype "bidirectional"))
      (node (ref "USB-LTE") (pin "SHLD1") (pinfunction "SHLD_SHLD1") (pintype "bidirectional"))
      (node (ref "USB-LTE") (pin "SHLD2") (pinfunction "SHLD_SHLD2") (pintype "bidirectional"))
      (node (ref "USB-LTE") (pin "SHLD3") (pinfunction "SHLD_SHLD3") (pintype "bidirectional"))
      (node (ref "USB-LTE") (pin "SHLD4") (pinfunction "SHLD_SHLD4") (pintype "bidirectional"))
      (node (ref "USB-LTE") (pin "SHLD5") (pinfunction "SHLD_SHLD5") (pintype "bidirectional"))
      (node (ref "USB-LTE") (pin "SHLD6") (pinfunction "SHLD_SHLD6") (pintype "bidirectional"))
      (node (ref "USB-LTE") (pin "SHLD7") (pinfunction "SHLD_SHLD7") (pintype "bidirectional"))
      (node (ref "USB-LTE") (pin "SHLD8") (pinfunction "SHLD_SHLD8") (pintype "bidirectional"))
      (node (ref "USB-NATIVE") (pin "GND") (pinfunction "GND_GND") (pintype "bidirectional"))
      (node (ref "USB-NATIVE") (pin "GND2") (pinfunction "GND_GND2") (pintype "bidirectional"))
      (node (ref "USB-NATIVE") (pin "SHLD1") (pinfunction "SHLD_SHLD1") (pintype "bidirectional"))
      (node (ref "USB-NATIVE") (pin "SHLD2") (pinfunction "SHLD_SHLD2") (pintype "bidirectional"))
      (node (ref "USB-NATIVE") (pin "SHLD3") (pinfunction "SHLD_SHLD3") (pintype "bidirectional"))
      (node (ref "USB-NATIVE") (pin "SHLD4") (pinfunction "SHLD_SHLD4") (pintype "bidirectional"))
      (node (ref "USB-NATIVE") (pin "SHLD5") (pinfunction "SHLD_SHLD5") (pintype "bidirectional"))
      (node (ref "USB-NATIVE") (pin "SHLD6") (pinfunction "SHLD_SHLD6") (pintype "bidirectional"))
      (node (ref "USB-NATIVE") (pin "SHLD7") (pinfunction "SHLD_SHLD7") (pintype "bidirectional"))
      (node (ref "USB-NATIVE") (pin "SHLD8") (pinfunction "SHLD_SHLD8") (pintype "bidirectional"))
      (node (ref "USB-TTL") (pin "GND") (pinfunction "GND_GND") (pintype "bidirectional"))
      (node (ref "USB-TTL") (pin "GND2") (pinfunction "GND_GND2") (pintype "bidirectional"))
      (node (ref "USB-TTL") (pin "SHLD1") (pinfunction "SHLD_SHLD1") (pintype "bidirectional"))
      (node (ref "USB-TTL") (pin "SHLD2") (pinfunction "SHLD_SHLD2") (pintype "bidirectional"))
      (node (ref "USB-TTL") (pin "SHLD3") (pinfunction "SHLD_SHLD3") (pintype "bidirectional"))
      (node (ref "USB-TTL") (pin "SHLD4") (pinfunction "SHLD_SHLD4") (pintype "bidirectional"))
      (node (ref "USB-TTL") (pin "SHLD5") (pinfunction "SHLD_SHLD5") (pintype "bidirectional"))
      (node (ref "USB-TTL") (pin "SHLD6") (pinfunction "SHLD_SHLD6") (pintype "bidirectional"))
      (node (ref "USB-TTL") (pin "SHLD7") (pinfunction "SHLD_SHLD7") (pintype "bidirectional"))
      (node (ref "USB-TTL") (pin "SHLD8") (pinfunction "SHLD_SHLD8") (pintype "bidirectional"))
    )
    (net (code "79") (name "Net-(BOOT-Pad1)") (class "Default")
      (node (ref "BOOT") (pin "1") (pinfunction "1_1") (pintype "passive"))
      (node (ref "R34") (pin "1") (pinfunction "1_1") (pintype "passive"))
    )
    (net (code "80") (name "Net-(C14-Pad2)") (class "Default")
      (node (ref "C14") (pin "2") (pinfunction "2_2") (pintype "passive"))
      (node (ref "C4") (pin "2") (pinfunction "2_2") (pintype "passive"))
      (node (ref "C55") (pin "1") (pinfunction "1_1") (pintype "passive"))
      (node (ref "C9") (pin "1") (pinfunction "1_1") (pintype "passive"))
      (node (ref "FB4") (pin "2") (pinfunction "2_2") (pintype "passive"))
    )
    (net (code "81") (name "Net-(C16-Pad2)") (class "Default")
      (node (ref "C16") (pin "2") (pinfunction "2_2") (pintype "passive"))
      (node (ref "R21") (pin "1") (pinfunction "1_1") (pintype "passive"))
      (node (ref "R37") (pin "1") (pinfunction "1_1") (pintype "passive"))
      (node (ref "R9") (pin "1") (pinfunction "1_1") (pintype "passive"))
    )
    (net (code "82") (name "Net-(C20-Pad2)") (class "Default")
      (node (ref "C20") (pin "2") (pinfunction "2_2") (pintype "passive"))
      (node (ref "C55") (pin "2") (pinfunction "2_2") (pintype "passive"))
      (node (ref "C56") (pin "1") (pinfunction "1_1") (pintype "passive"))
      (node (ref "C57") (pin "1") (pinfunction "1_1") (pintype "passive"))
      (node (ref "C9") (pin "2") (pinfunction "2_2") (pintype "passive"))
      (node (ref "FB3") (pin "2") (pinfunction "2_2") (pintype "passive"))
      (node (ref "R51") (pin "2") (pinfunction "2_2") (pintype "passive"))
      (node (ref "R9") (pin "2") (pinfunction "2_2") (pintype "passive"))
    )
    (net (code "83") (name "Net-(C28-Pad1)") (class "Default")
      (node (ref "C28") (pin "1") (pinfunction "1_1") (pintype "passive"))
      (node (ref "C78") (pin "1") (pinfunction "1_1") (pintype "passive"))
      (node (ref "C79") (pin "2") (pinfunction "2_2") (pintype "passive"))
      (node (ref "C81") (pin "1") (pinfunction "1_1") (pintype "passive"))
      (node (ref "C83") (pin "2") (pinfunction "2_2") (pintype "passive"))
      (node (ref "R66") (pin "1") (pinfunction "1_1") (pintype "passive"))
    )
    (net (code "84") (name "Net-(C28-Pad2)") (class "Default")
      (node (ref "C28") (pin "2") (pinfunction "2_2") (pintype "passive"))
      (node (ref "EAR") (pin "4") (pinfunction "4_4") (pintype "bidirectional"))
    )
    (net (code "85") (name "Net-(C37-Pad1)") (class "Default")
      (node (ref "C37") (pin "1") (pinfunction "1_1") (pintype "passive"))
      (node (ref "C78") (pin "2") (pinfunction "2_2") (pintype "passive"))
      (node (ref "C80") (pin "1") (pinfunction "1_1") (pintype "passive"))
      (node (ref "C81") (pin "2") (pinfunction "2_2") (pintype "passive"))
      (node (ref "C82") (pin "1") (pinfunction "1_1") (pintype "passive"))
      (node (ref "R65") (pin "1") (pinfunction "1_1") (pintype "passive"))
    )
    (net (code "86") (name "Net-(C37-Pad2)") (class "Default")
      (node (ref "C37") (pin "2") (pinfunction "2_2") (pintype "passive"))
      (node (ref "EAR") (pin "3") (pinfunction "3_3") (pintype "bidirectional"))
    )
    (net (code "87") (name "Net-(C43-Pad2)") (class "Default")
      (node (ref "C43") (pin "2") (pinfunction "2_2") (pintype "passive"))
      (node (ref "R20") (pin "1") (pinfunction "1_1") (pintype "passive"))
      (node (ref "R39") (pin "2") (pinfunction "2_2") (pintype "passive"))
    )
    (net (code "88") (name "Net-(C44-Pad1)") (class "Default")
      (node (ref "C44") (pin "1") (pinfunction "1_1") (pintype "passive"))
      (node (ref "L1") (pin "1") (pinfunction "1_1") (pintype "passive"))
      (node (ref "R40") (pin "1") (pinfunction "1_1") (pintype "passive"))
    )
    (net (code "89") (name "Net-(C45-Pad1)") (class "Default")
      (node (ref "C45") (pin "1") (pinfunction "1_1") (pintype "passive"))
      (node (ref "GPS") (pin "D") (pinfunction "D_D") (pintype "bidirectional"))
      (node (ref "L1") (pin "2") (pinfunction "2_2") (pintype "passive"))
    )
    (net (code "90") (name "Net-(C45-Pad2)") (class "Default")
      (node (ref "C45") (pin "2") (pinfunction "2_2") (pintype "passive"))
      (node (ref "U5") (pin "90") (pinfunction "NC_90") (pintype "bidirectional"))
    )
    (net (code "91") (name "Net-(C58-Pad2)") (class "Default")
      (node (ref "C58") (pin "2") (pinfunction "2_2") (pintype "passive"))
      (node (ref "D6") (pin "-") (pinfunction "-_-") (pintype "passive"))
      (node (ref "U5") (pin "116") (pinfunction "NC_116") (pintype "bidirectional"))
    )
    (net (code "92") (name "Net-(CHRG-PadC)") (class "Default")
      (node (ref "CHRG") (pin "C") (pinfunction "C_C") (pintype "passive"))
      (node (ref "R13") (pin "1") (pinfunction "1_1") (pintype "passive"))
    )
    (net (code "93") (name "Net-(D13-Pad-)") (class "Default")
      (node (ref "D13") (pin "-") (pinfunction "-_-") (pintype "passive"))
      (node (ref "LTE") (pin "D") (pinfunction "D_D") (pintype "bidirectional"))
      (node (ref "R20") (pin "2") (pinfunction "2_2") (pintype "passive"))
    )
    (net (code "94") (name "Net-(DONE-PadC)") (class "Default")
      (node (ref "DONE") (pin "C") (pinfunction "C_C") (pintype "passive"))
      (node (ref "R17") (pin "1") (pinfunction "1_1") (pintype "passive"))
    )
    (net (code "95") (name "Net-(EAR-Pad1)") (class "Default")
      (node (ref "EAR") (pin "1") (pinfunction "1_1") (pintype "bidirectional"))
      (node (ref "R30") (pin "1") (pinfunction "1_1") (pintype "passive"))
      (node (ref "R37") (pin "2") (pinfunction "2_2") (pintype "passive"))
    )
    (net (code "96") (name "Net-(EAR-Pad2)") (class "Default")
      (node (ref "EAR") (pin "2") (pinfunction "2_2") (pintype "bidirectional"))
      (node (ref "R21") (pin "2") (pinfunction "2_2") (pintype "passive"))
      (node (ref "R25") (pin "1") (pinfunction "1_1") (pintype "passive"))
    )
    (net (code "97") (name "Net-(FB1-Pad2)") (class "Default")
      (node (ref "FB1") (pin "2") (pinfunction "2_2") (pintype "passive"))
      (node (ref "R65") (pin "2") (pinfunction "2_2") (pintype "passive"))
    )
    (net (code "98") (name "Net-(FB2-Pad1)") (class "Default")
      (node (ref "FB2") (pin "1") (pinfunction "1_1") (pintype "passive"))
      (node (ref "R66") (pin "2") (pinfunction "2_2") (pintype "passive"))
    )
    (net (code "99") (name "Net-(NET-PadA)") (class "Default")
      (node (ref "NET") (pin "A") (pinfunction "A_A") (pintype "passive"))
      (node (ref "R18") (pin "1") (pinfunction "1_1") (pintype "passive"))
    )
    (net (code "100") (name "Net-(Q1-G)") (class "Default")
      (node (ref "Q1") (pin "1") (pinfunction "G_1") (pintype "passive"))
      (node (ref "R31") (pin "1") (pinfunction "1_1") (pintype "passive"))
      (node (ref "R32") (pin "2") (pinfunction "2_2") (pintype "passive"))
    )
    (net (code "101") (name "Net-(Q3-G)") (class "Default")
      (node (ref "Q3") (pin "1") (pinfunction "G_1") (pintype "passive"))
      (node (ref "R35") (pin "1") (pinfunction "1_1") (pintype "passive"))
      (node (ref "R36") (pin "2") (pinfunction "2_2") (pintype "passive"))
    )
    (net (code "102") (name "Net-(Q4-D)") (class "Default")
      (node (ref "Q4") (pin "3") (pinfunction "D_3") (pintype "passive"))
      (node (ref "STA") (pin "C") (pinfunction "C_C") (pintype "passive"))
    )
    (net (code "103") (name "Net-(Q4-G)") (class "Default")
      (node (ref "Q4") (pin "1") (pinfunction "G_1") (pintype "passive"))
      (node (ref "R41") (pin "1") (pinfunction "1_1") (pintype "passive"))
      (node (ref "R42") (pin "2") (pinfunction "2_2") (pintype "passive"))
    )
    (net (code "104") (name "Net-(Q6-D)") (class "Default")
      (node (ref "NET") (pin "C") (pinfunction "C_C") (pintype "passive"))
      (node (ref "Q6") (pin "3") (pinfunction "D_3") (pintype "passive"))
    )
    (net (code "105") (name "Net-(Q6-G)") (class "Default")
      (node (ref "Q6") (pin "1") (pinfunction "G_1") (pintype "passive"))
      (node (ref "R14") (pin "2") (pinfunction "2_2") (pintype "passive"))
      (node (ref "R16") (pin "1") (pinfunction "1_1") (pintype "passive"))
    )
    (net (code "106") (name "Net-(Q10-B)") (class "Default")
      (node (ref "Q10") (pin "1") (pinfunction "B_1") (pintype "passive"))
      (node (ref "R63") (pin "1") (pinfunction "1_1") (pintype "passive"))
    )
    (net (code "107") (name "Net-(Q11-B)") (class "Default")
      (node (ref "Q11") (pin "1") (pinfunction "B_1") (pintype "passive"))
      (node (ref "R62") (pin "1") (pinfunction "1_1") (pintype "passive"))
    )
    (net (code "108") (name "Net-(R28-Pad2)") (class "Default")
      (node (ref "R28") (pin "2") (pinfunction "2_2") (pintype "passive"))
      (node (ref "USB-LTE") (pin "A6") (pinfunction "D+_A6") (pintype "bidirectional"))
      (node (ref "USB-LTE") (pin "B6") (pinfunction "D+_B6") (pintype "bidirectional"))
    )
    (net (code "109") (name "Net-(R29-Pad2)") (class "Default")
      (node (ref "R29") (pin "2") (pinfunction "2_2") (pintype "passive"))
      (node (ref "USB-LTE") (pin "A7") (pinfunction "D-_A7") (pintype "bidirectional"))
      (node (ref "USB-LTE") (pin "B7") (pinfunction "D-_B7") (pintype "bidirectional"))
    )
    (net (code "110") (name "Net-(R38-Pad1)") (class "Default")
      (node (ref "R38") (pin "1") (pinfunction "1_1") (pintype "passive"))
      (node (ref "STA") (pin "A") (pinfunction "A_A") (pintype "passive"))
    )
    (net (code "111") (name "Net-(R52-Pad1)") (class "Default")
      (node (ref "R52") (pin "1") (pinfunction "1_1") (pintype "passive"))
      (node (ref "U5") (pin "95") (pinfunction "NC_95") (pintype "bidirectional"))
    )
    (net (code "112") (name "Net-(R53-Pad1)") (class "Default")
      (node (ref "R53") (pin "1") (pinfunction "1_1") (pintype "passive"))
      (node (ref "U5") (pin "96") (pinfunction "NC_96") (pintype "bidirectional"))
    )
    (net (code "113") (name "Net-(SD-DATA1)") (class "Default")
      (node (ref "R72") (pin "1") (pinfunction "1_1") (pintype "passive"))
      (node (ref "SD") (pin "8") (pinfunction "DATA1_8") (pintype "bidirectional"))
    )
    (net (code "114") (name "Net-(SD-DATA2)") (class "Default")
      (node (ref "R70") (pin "1") (pinfunction "1_1") (pintype "passive"))
      (node (ref "SD") (pin "1") (pinfunction "DATA2_1") (pintype "bidirectional"))
    )
    (net (code "115") (name "Net-(U1-V)") (class "Default")
      (node (ref "R8") (pin "2") (pinfunction "2_2") (pintype "passive"))
      (node (ref "U1") (pin "1") (pinfunction "V_1") (pintype "bidirectional"))
    )
    (net (code "116") (name "Net-(U1-VDD)") (class "Default")
      (node (ref "C25") (pin "2") (pinfunction "2_2") (pintype "passive"))
      (node (ref "R11") (pin "2") (pinfunction "2_2") (pintype "passive"))
      (node (ref "U1") (pin "5") (pinfunction "VDD_5") (pintype "bidirectional"))
    )
    (net (code "117") (name "Net-(U2-EN)") (class "Default")
      (node (ref "R77") (pin "1") (pinfunction "1_1") (pintype "passive"))
      (node (ref "U2") (pin "8") (pinfunction "EN_8") (pintype "bidirectional"))
    )
    (net (code "118") (name "Net-(U2-FB)") (class "Default")
      (node (ref "C61") (pin "1") (pinfunction "1_1") (pintype "passive"))
      (node (ref "R74") (pin "2") (pinfunction "2_2") (pintype "passive"))
      (node (ref "R75") (pin "1") (pinfunction "1_1") (pintype "passive"))
      (node (ref "U2") (pin "7") (pinfunction "FB_7") (pintype "bidirectional"))
    )
    (net (code "119") (name "Net-(U2-PG)") (class "Default")
      (node (ref "R76") (pin "1") (pinfunction "1_1") (pintype "passive"))
      (node (ref "U2") (pin "1") (pinfunction "PG_1") (pintype "bidirectional"))
    )
    (net (code "120") (name "Net-(U2-SW)") (class "Default")
      (node (ref "L2") (pin "1") (pinfunction "1_1") (pintype "passive"))
      (node (ref "U2") (pin "3") (pinfunction "SW_3") (pintype "bidirectional"))
    )
    (net (code "121") (name "Net-(U3-CHRG)") (class "Default")
      (node (ref "R13") (pin "2") (pinfunction "2_2") (pintype "passive"))
      (node (ref "U3") (pin "7") (pinfunction "CHRG_7") (pintype "bidirectional"))
    )
    (net (code "122") (name "Net-(U3-DONE)") (class "Default")
      (node (ref "R17") (pin "2") (pinfunction "2_2") (pintype "passive"))
      (node (ref "U3") (pin "6") (pinfunction "DONE_6") (pintype "bidirectional"))
    )
    (net (code "123") (name "Net-(U3-ISET)") (class "Default")
      (node (ref "R12") (pin "1") (pinfunction "1_1") (pintype "passive"))
      (node (ref "U3") (pin "2") (pinfunction "ISET_2") (pintype "bidirectional"))
    )
    (net (code "124") (name "Net-(U5-USIM1_CLK)") (class "Default")
      (node (ref "R23") (pin "1") (pinfunction "1_1") (pintype "passive"))
      (node (ref "U5") (pin "32") (pinfunction "USIM1_CLK_32") (pintype "bidirectional"))
    )
    (net (code "125") (name "Net-(U5-USIM1_DATA)") (class "Default")
      (node (ref "R22") (pin "1") (pinfunction "1_1") (pintype "passive"))
      (node (ref "U5") (pin "31") (pinfunction "USIM1_DATA_31") (pintype "bidirectional"))
    )
    (net (code "126") (name "Net-(U5-USIM1_RST)") (class "Default")
      (node (ref "R24") (pin "1") (pinfunction "1_1") (pintype "passive"))
      (node (ref "U5") (pin "33") (pinfunction "USIM1_RST_33") (pintype "bidirectional"))
    )
    (net (code "127") (name "Net-(U7-RXD)") (class "Default")
      (node (ref "R69") (pin "2") (pinfunction "2_2") (pintype "passive"))
      (node (ref "U7") (pin "9") (pinfunction "RXD_9") (pintype "bidirectional"))
    )
    (net (code "128") (name "Net-(U7-TXD)") (class "Default")
      (node (ref "R68") (pin "2") (pinfunction "2_2") (pintype "passive"))
      (node (ref "U7") (pin "8") (pinfunction "TXD_8") (pintype "bidirectional"))
    )
    (net (code "129") (name "Net-(USB-LTE-CC1)") (class "Default")
      (node (ref "R27") (pin "2") (pinfunction "2_2") (pintype "passive"))
      (node (ref "USB-LTE") (pin "A5") (pinfunction "CC1_A5") (pintype "bidirectional"))
    )
    (net (code "130") (name "Net-(USB-LTE-CC2)") (class "Default")
      (node (ref "R26") (pin "2") (pinfunction "2_2") (pintype "passive"))
      (node (ref "USB-LTE") (pin "B5") (pinfunction "CC2_B5") (pintype "bidirectional"))
    )
    (net (code "131") (name "Net-(USB-NATIVE-CC1)") (class "Default")
      (node (ref "R61") (pin "2") (pinfunction "2_2") (pintype "passive"))
      (node (ref "USB-NATIVE") (pin "A5") (pinfunction "CC1_A5") (pintype "bidirectional"))
    )
    (net (code "132") (name "Net-(USB-NATIVE-CC2)") (class "Default")
      (node (ref "R60") (pin "2") (pinfunction "2_2") (pintype "passive"))
      (node (ref "USB-NATIVE") (pin "B5") (pinfunction "CC2_B5") (pintype "bidirectional"))
    )
    (net (code "133") (name "Net-(USB-TTL-CC1)") (class "Default")
      (node (ref "R67") (pin "2") (pinfunction "2_2") (pintype "passive"))
      (node (ref "USB-TTL") (pin "A5") (pinfunction "CC1_A5") (pintype "bidirectional"))
    )
    (net (code "134") (name "Net-(USB-TTL-CC2)") (class "Default")
      (node (ref "R64") (pin "2") (pinfunction "2_2") (pintype "passive"))
      (node (ref "USB-TTL") (pin "B5") (pinfunction "CC2_B5") (pintype "bidirectional"))
    )
    (net (code "135") (name "VBAT+") (class "Default")
      (node (ref "BAT") (pin "2") (pinfunction "2_2") (pintype "bidirectional"))
      (node (ref "C7") (pin "1") (pinfunction "1_1") (pintype "passive"))
      (node (ref "J3") (pin "1") (pinfunction "1_1") (pintype "passive"))
      (node (ref "J5") (pin "13") (pinfunction "13_13") (pintype "bidirectional"))
      (node (ref "R1") (pin "2") (pinfunction "2_2") (pintype "passive"))
      (node (ref "R11") (pin "1") (pinfunction "1_1") (pintype "passive"))
      (node (ref "SW1") (pin "COM1") (pinfunction "COM1_COM1") (pintype "bidirectional"))
      (node (ref "U3") (pin "5") (pinfunction "BAT_5") (pintype "bidirectional"))
    )
    (net (code "136") (name "VBUS") (class "Default")
      (node (ref "C49") (pin "2") (pinfunction "2_2") (pintype "passive"))
      (node (ref "C50") (pin "2") (pinfunction "2_2") (pintype "passive"))
      (node (ref "C54") (pin "2") (pinfunction "2_2") (pintype "passive"))
      (node (ref "D3") (pin "A") (pinfunction "A_A") (pintype "passive"))
      (node (ref "J1") (pin "1") (pinfunction "1_1") (pintype "bidirectional"))
      (node (ref "USB-TTL") (pin "VBUS1") (pinfunction "VBUS_VBUS1") (pintype "bidirectional"))
      (node (ref "USB-TTL") (pin "VBUS2") (pinfunction "VBUS_VBUS2") (pintype "bidirectional"))
    )
    (net (code "137") (name "VDD") (class "Default")
      (node (ref "3V") (pin "T") (pinfunction "T_T") (pintype "bidirectional"))
      (node (ref "C30") (pin "2") (pinfunction "2_2") (pintype "passive"))
      (node (ref "C31") (pin "2") (pinfunction "2_2") (pintype "passive"))
      (node (ref "R51") (pin "1") (pinfunction "1_1") (pintype "passive"))
      (node (ref "U5") (pin "99") (pinfunction "VDD_AUX_99") (pintype "bidirectional"))
    )
    (net (code "138") (name "V_BATT") (class "Default")
      (node (ref "C18") (pin "2") (pinfunction "2_2") (pintype "passive"))
      (node (ref "C19") (pin "2") (pinfunction "2_2") (pintype "passive"))
      (node (ref "C22") (pin "2") (pinfunction "2_2") (pintype "passive"))
      (node (ref "C23") (pin "2") (pinfunction "2_2") (pintype "passive"))
      (node (ref "C24") (pin "2") (pinfunction "2_2") (pintype "passive"))
      (node (ref "C26") (pin "A") (pinfunction "+_A") (pintype "passive"))
      (node (ref "C46") (pin "2") (pinfunction "2_2") (pintype "passive"))
      (node (ref "C47") (pin "2") (pinfunction "2_2") (pintype "passive"))
      (node (ref "C48") (pin "A") (pinfunction "+_A") (pintype "passive"))
      (node (ref "D7") (pin "-") (pinfunction "-_-") (pintype "passive"))
      (node (ref "D8") (pin "C") (pinfunction "C_C") (pintype "passive"))
      (node (ref "R18") (pin "2") (pinfunction "2_2") (pintype "passive"))
      (node (ref "R38") (pin "2") (pinfunction "2_2") (pintype "passive"))
      (node (ref "R6") (pin "1") (pinfunction "1_1") (pintype "passive"))
      (node (ref "R78") (pin "1") (pinfunction "1_1") (pintype "passive"))
      (node (ref "U5") (pin "55") (pinfunction "VBAT_55") (pintype "bidirectional"))
      (node (ref "U5") (pin "56") (pinfunction "VBAT_56") (pintype "bidirectional"))
      (node (ref "U5") (pin "57") (pinfunction "VBAT_57") (pintype "bidirectional"))
    )
    (net (code "139") (name "unconnected-(D10-C1-Pad1)") (class "Default")
      (node (ref "D10") (pin "1") (pinfunction "C1_1") (pintype "passive"))
    )
    (net (code "140") (name "unconnected-(EAR-Pad5)") (class "Default")
      (node (ref "EAR") (pin "5") (pinfunction "5_5") (pintype "bidirectional"))
    )
    (net (code "141") (name "unconnected-(EAR-Pad6)") (class "Default")
      (node (ref "EAR") (pin "6") (pinfunction "6_6") (pintype "bidirectional"))
    )
    (net (code "142") (name "unconnected-(EAR-Pad7)") (class "Default")
      (node (ref "EAR") (pin "7") (pinfunction "7_7") (pintype "bidirectional"))
    )
    (net (code "143") (name "unconnected-(EAR-Pad8)") (class "Default")
      (node (ref "EAR") (pin "8") (pinfunction "8_8") (pintype "bidirectional"))
    )
    (net (code "144") (name "unconnected-(SD-CDN-Pad9)") (class "Default")
      (node (ref "SD") (pin "9") (pinfunction "CDN_9") (pintype "bidirectional"))
    )
    (net (code "145") (name "unconnected-(SIM-VPP-Pad6)") (class "Default")
      (node (ref "SIM") (pin "6") (pinfunction "VPP_6") (pintype "bidirectional"))
    )
    (net (code "146") (name "unconnected-(SW1-PadCH1B)") (class "Default")
      (node (ref "SW1") (pin "CH1B") (pinfunction "CH1B_CH1B") (pintype "bidirectional"))
    )
    (net (code "147") (name "unconnected-(SW1-PadCH2B)") (class "Default")
      (node (ref "SW1") (pin "CH2B") (pinfunction "CH2B_CH2B") (pintype "bidirectional"))
    )
    (net (code "148") (name "unconnected-(U1-D-Pad4)") (class "Default")
      (node (ref "U1") (pin "4") (pinfunction "D_4") (pintype "bidirectional"))
    )
    (net (code "149") (name "unconnected-(U4-BYP-Pad4)") (class "Default")
      (node (ref "U4") (pin "4") (pinfunction "BYP_4") (pintype "bidirectional"))
    )
    (net (code "150") (name "unconnected-(U5-ADC-Pad25)") (class "Default")
      (node (ref "U5") (pin "25") (pinfunction "ADC_25") (pintype "bidirectional"))
    )
    (net (code "151") (name "unconnected-(U5-CAM_I2C_SCL-Pad118)") (class "Default")
      (node (ref "U5") (pin "118") (pinfunction "CAM_I2C_SCL_118") (pintype "bidirectional"))
    )
    (net (code "152") (name "unconnected-(U5-CAM_I2C_SDA-Pad117)") (class "Default")
      (node (ref "U5") (pin "117") (pinfunction "CAM_I2C_SDA_117") (pintype "bidirectional"))
    )
    (net (code "153") (name "unconnected-(U5-CAM_MCLK-Pad121)") (class "Default")
      (node (ref "U5") (pin "121") (pinfunction "CAM_MCLK_121") (pintype "bidirectional"))
    )
    (net (code "154") (name "unconnected-(U5-CAM_PWDN-Pad119)") (class "Default")
      (node (ref "U5") (pin "119") (pinfunction "CAM_PWDN_119") (pintype "bidirectional"))
    )
    (net (code "155") (name "unconnected-(U5-CAM_RST-Pad120)") (class "Default")
      (node (ref "U5") (pin "120") (pinfunction "CAM_RST_120") (pintype "bidirectional"))
    )
    (net (code "156") (name "unconnected-(U5-CAM_SPI_CLK-Pad124)") (class "Default")
      (node (ref "U5") (pin "124") (pinfunction "CAM_SPI_CLK_124") (pintype "bidirectional"))
    )
    (net (code "157") (name "unconnected-(U5-CAM_SPI_D0-Pad122)") (class "Default")
      (node (ref "U5") (pin "122") (pinfunction "CAM_SPI_D0_122") (pintype "bidirectional"))
    )
    (net (code "158") (name "unconnected-(U5-CAM_SPI_D1-Pad123)") (class "Default")
      (node (ref "U5") (pin "123") (pinfunction "CAM_SPI_D1_123") (pintype "bidirectional"))
    )
    (net (code "159") (name "unconnected-(U5-CTS-Pad7)") (class "Default")
      (node (ref "U5") (pin "7") (pinfunction "CTS_7") (pintype "bidirectional"))
    )
    (net (code "160") (name "unconnected-(U5-DCD-Pad5)") (class "Default")
      (node (ref "U5") (pin "5") (pinfunction "DCD_5") (pintype "bidirectional"))
    )
    (net (code "161") (name "unconnected-(U5-GPIO1-Pad19)") (class "Default")
      (node (ref "U5") (pin "19") (pinfunction "GPIO1_19") (pintype "bidirectional"))
    )
    (net (code "162") (name "unconnected-(U5-GPIO2-Pad26)") (class "Default")
      (node (ref "U5") (pin "26") (pinfunction "GPIO2_26") (pintype "bidirectional"))
    )
    (net (code "163") (name "unconnected-(U5-GPIO3-Pad48)") (class "Default")
      (node (ref "U5") (pin "48") (pinfunction "GPIO3_48") (pintype "bidirectional"))
    )
    (net (code "164") (name "unconnected-(U5-GPIO4-Pad53)") (class "Default")
      (node (ref "U5") (pin "53") (pinfunction "GPIO4_53") (pintype "bidirectional"))
    )
    (net (code "165") (name "unconnected-(U5-I2C_SCL-Pad38)") (class "Default")
      (node (ref "U5") (pin "38") (pinfunction "I2C_SCL_38") (pintype "bidirectional"))
    )
    (net (code "166") (name "unconnected-(U5-I2C_SDA-Pad37)") (class "Default")
      (node (ref "U5") (pin "37") (pinfunction "I2C_SDA_37") (pintype "bidirectional"))
    )
    (net (code "167") (name "unconnected-(U5-LCD_BL_PWM-Pad101)") (class "Default")
      (node (ref "U5") (pin "101") (pinfunction "LCD_BL_PWM_101") (pintype "bidirectional"))
    )
    (net (code "168") (name "unconnected-(U5-LCD_DCX-Pad107)") (class "Default")
      (node (ref "U5") (pin "107") (pinfunction "LCD_DCX_107") (pintype "bidirectional"))
    )
    (net (code "169") (name "unconnected-(U5-LCD_RST-Pad106)") (class "Default")
      (node (ref "U5") (pin "106") (pinfunction "LCD_RST_106") (pintype "bidirectional"))
    )
    (net (code "170") (name "unconnected-(U5-LCD_SPI_CLK-Pad102)") (class "Default")
      (node (ref "U5") (pin "102") (pinfunction "LCD_SPI_CLK_102") (pintype "bidirectional"))
    )
    (net (code "171") (name "unconnected-(U5-LCD_SPI_CS-Pad105)") (class "Default")
      (node (ref "U5") (pin "105") (pinfunction "LCD_SPI_CS_105") (pintype "bidirectional"))
    )
    (net (code "172") (name "unconnected-(U5-LCD_SPI_RXD-Pad104)") (class "Default")
      (node (ref "U5") (pin "104") (pinfunction "LCD_SPI_RXD_104") (pintype "bidirectional"))
    )
    (net (code "173") (name "unconnected-(U5-LCD_SPI_TXD-Pad103)") (class "Default")
      (node (ref "U5") (pin "103") (pinfunction "LCD_SPI_TXD_103") (pintype "bidirectional"))
    )
    (net (code "174") (name "unconnected-(U5-MK_IN_2-Pad47)") (class "Default")
      (node (ref "U5") (pin "47") (pinfunction "MK_IN_2_47") (pintype "bidirectional"))
    )
    (net (code "175") (name "unconnected-(U5-MK_IN_5-Pad68)") (class "Default")
      (node (ref "U5") (pin "68") (pinfunction "MK_IN_5_68") (pintype "bidirectional"))
    )
    (net (code "176") (name "unconnected-(U5-MK_IN_6-Pad36)") (class "Default")
      (node (ref "U5") (pin "36") (pinfunction "MK_IN_6_36") (pintype "bidirectional"))
    )
    (net (code "177") (name "unconnected-(U5-MK_OUT_2-Pad44)") (class "Default")
      (node (ref "U5") (pin "44") (pinfunction "MK_OUT_2_44") (pintype "bidirectional"))
    )
    (net (code "178") (name "unconnected-(U5-MK_OUT_3-Pad21)") (class "Default")
      (node (ref "U5") (pin "21") (pinfunction "MK_OUT_3_21") (pintype "bidirectional"))
    )
    (net (code "179") (name "unconnected-(U5-MK_OUT_5-Pad67)") (class "Default")
      (node (ref "U5") (pin "67") (pinfunction "MK_OUT_5_67") (pintype "bidirectional"))
    )
    (net (code "180") (name "unconnected-(U5-MK_OUT_6-Pad35)") (class "Default")
      (node (ref "U5") (pin "35") (pinfunction "MK_OUT_6_35") (pintype "bidirectional"))
    )
    (net (code "181") (name "unconnected-(U5-NC-Pad93)") (class "Default")
      (node (ref "U5") (pin "93") (pinfunction "NC_93") (pintype "bidirectional"))
    )
    (net (code "182") (name "unconnected-(U5-NC-Pad100)") (class "Default")
      (node (ref "U5") (pin "100") (pinfunction "NC_100") (pintype "bidirectional"))
    )
    (net (code "183") (name "unconnected-(U5-NC-Pad113)") (class "Default")
      (node (ref "U5") (pin "113") (pinfunction "NC_113") (pintype "bidirectional"))
    )
    (net (code "184") (name "unconnected-(U5-NC-Pad114)") (class "Default")
      (node (ref "U5") (pin "114") (pinfunction "NC_114") (pintype "bidirectional"))
    )
    (net (code "185") (name "unconnected-(U5-NC-Pad115)") (class "Default")
      (node (ref "U5") (pin "115") (pinfunction "NC_115") (pintype "bidirectional"))
    )
    (net (code "186") (name "unconnected-(U5-RTS-Pad8)") (class "Default")
      (node (ref "U5") (pin "8") (pinfunction "RTS_8") (pintype "bidirectional"))
    )
    (net (code "187") (name "unconnected-(U5-SPI_CLK-Pad11)") (class "Default")
      (node (ref "U5") (pin "11") (pinfunction "SPI_CLK_11") (pintype "bidirectional"))
    )
    (net (code "188") (name "unconnected-(U5-SPI_CS-Pad12)") (class "Default")
      (node (ref "U5") (pin "12") (pinfunction "SPI_CS_12") (pintype "bidirectional"))
    )
    (net (code "189") (name "unconnected-(U5-SPI_MISO-Pad14)") (class "Default")
      (node (ref "U5") (pin "14") (pinfunction "SPI_MISO_14") (pintype "bidirectional"))
    )
    (net (code "190") (name "unconnected-(U5-SPI_MOSI-Pad13)") (class "Default")
      (node (ref "U5") (pin "13") (pinfunction "SPI_MOSI_13") (pintype "bidirectional"))
    )
    (net (code "191") (name "unconnected-(U5-USIM1_DET-Pad34)") (class "Default")
      (node (ref "U5") (pin "34") (pinfunction "USIM1_DET_34") (pintype "bidirectional"))
    )
    (net (code "192") (name "unconnected-(U5-USIM2_CLK-Pad109)") (class "Default")
      (node (ref "U5") (pin "109") (pinfunction "USIM2_CLK_109") (pintype "bidirectional"))
    )
    (net (code "193") (name "unconnected-(U5-USIM2_DATA-Pad108)") (class "Default")
      (node (ref "U5") (pin "108") (pinfunction "USIM2_DATA_108") (pintype "bidirectional"))
    )
    (net (code "194") (name "unconnected-(U5-USIM2_DET-Pad112)") (class "Default")
      (node (ref "U5") (pin "112") (pinfunction "USIM2_DET_112") (pintype "bidirectional"))
    )
    (net (code "195") (name "unconnected-(U5-USIM2_RST-Pad111)") (class "Default")
      (node (ref "U5") (pin "111") (pinfunction "USIM2_RST_111") (pintype "bidirectional"))
    )
    (net (code "196") (name "unconnected-(U5-USIM2_VDD-Pad110)") (class "Default")
      (node (ref "U5") (pin "110") (pinfunction "USIM2_VDD_110") (pintype "bidirectional"))
    )
    (net (code "197") (name "unconnected-(U6-IO35-Pad28)") (class "Default")
      (node (ref "U6") (pin "28") (pinfunction "IO35_28") (pintype "bidirectional"))
    )
    (net (code "198") (name "unconnected-(U6-IO36-Pad29)") (class "Default")
      (node (ref "U6") (pin "29") (pinfunction "IO36_29") (pintype "bidirectional"))
    )
    (net (code "199") (name "unconnected-(U6-IO37-Pad30)") (class "Default")
      (node (ref "U6") (pin "30") (pinfunction "IO37_30") (pintype "bidirectional"))
    )
    (net (code "200") (name "unconnected-(U7-CTS#-Pad5)") (class "Default")
      (node (ref "U7") (pin "5") (pinfunction "CTS#_5") (pintype "bidirectional"))
    )
  )
)
